# Sheet_1.net
KiCad netlist of a schematic drawn in EasyEDA
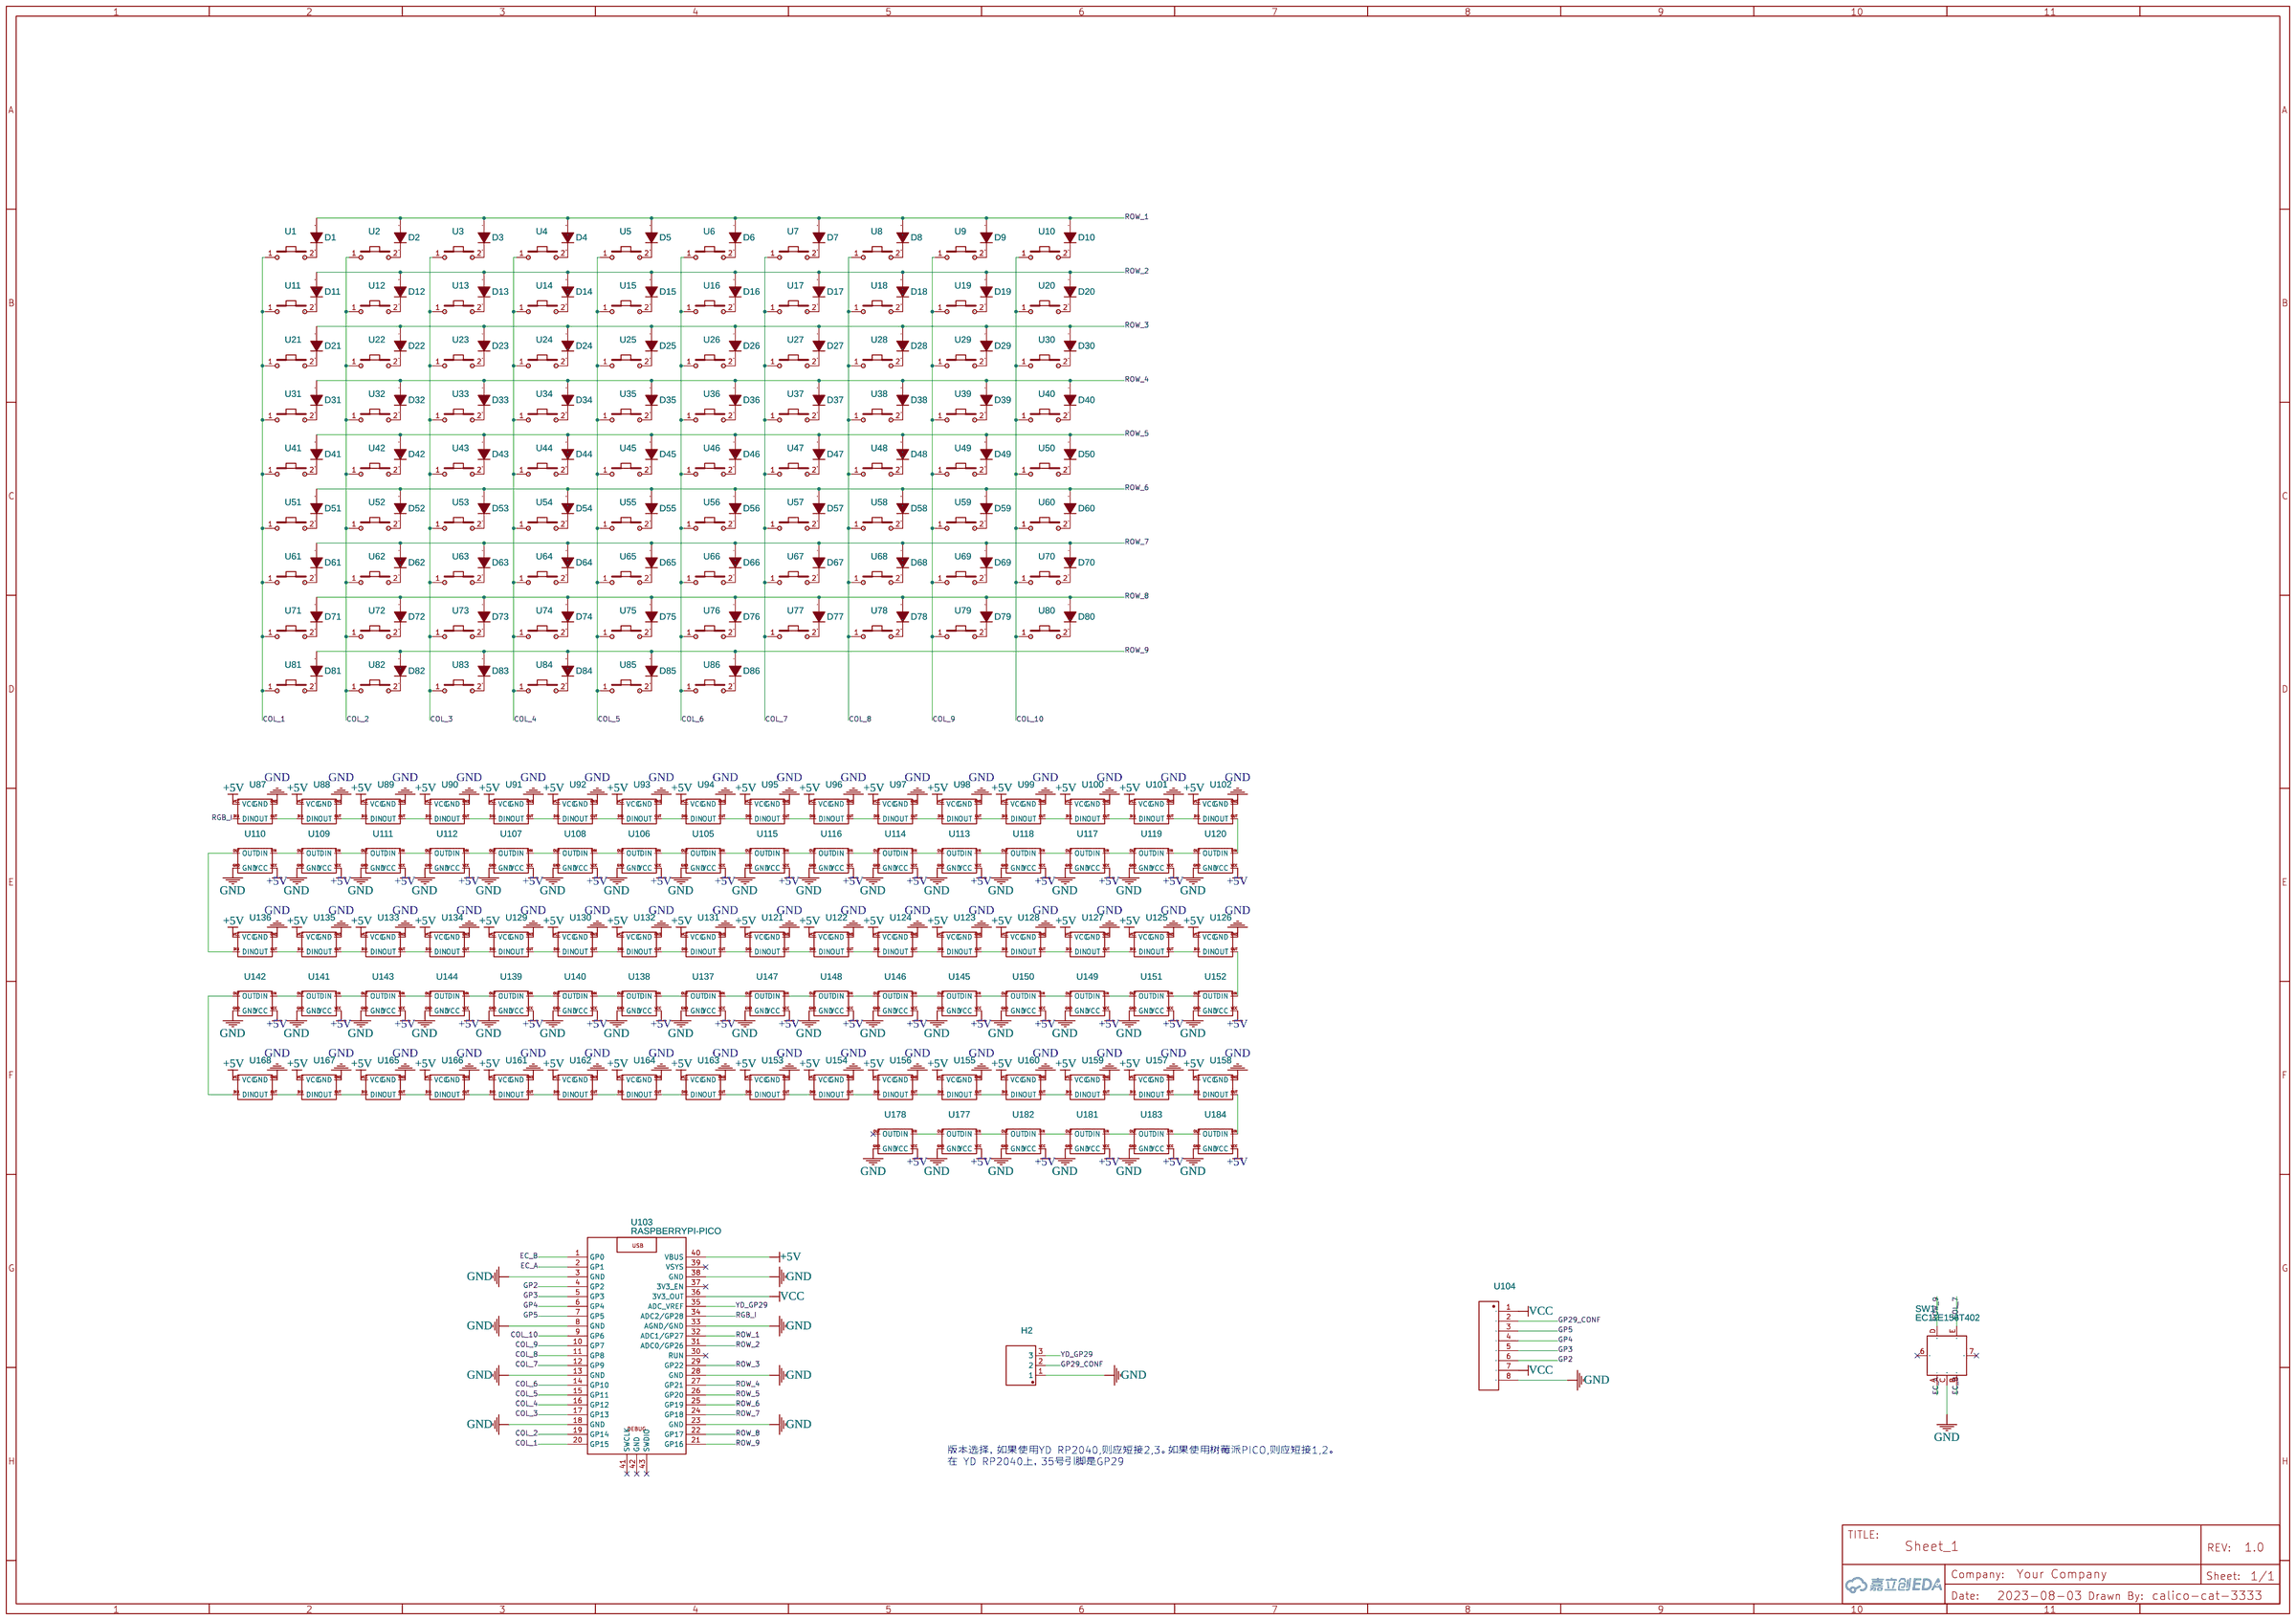
[diagram p0: schematic sheet]

(export (version "E")
  (design (tool "Eeschema 10.0.6"))
  (components
    (comp (ref "D1")
      (value "TC1N4148T26B")
      (fields (field (name "Manufacturer") "TC(德昌)"))
      (libsource (lib "") (part "TC1N4148T26B"))
    )
    (comp (ref "D2")
      (value "TC1N4148T26B")
      (fields (field (name "Manufacturer") "TC(德昌)"))
      (libsource (lib "") (part "TC1N4148T26B"))
    )
    (comp (ref "D3")
      (value "TC1N4148T26B")
      (fields (field (name "Manufacturer") "TC(德昌)"))
      (libsource (lib "") (part "TC1N4148T26B"))
    )
    (comp (ref "D4")
      (value "TC1N4148T26B")
      (fields (field (name "Manufacturer") "TC(德昌)"))
      (libsource (lib "") (part "TC1N4148T26B"))
    )
    (comp (ref "D5")
      (value "TC1N4148T26B")
      (fields (field (name "Manufacturer") "TC(德昌)"))
      (libsource (lib "") (part "TC1N4148T26B"))
    )
    (comp (ref "D6")
      (value "TC1N4148T26B")
      (fields (field (name "Manufacturer") "TC(德昌)"))
      (libsource (lib "") (part "TC1N4148T26B"))
    )
    (comp (ref "D7")
      (value "TC1N4148T26B")
      (fields (field (name "Manufacturer") "TC(德昌)"))
      (libsource (lib "") (part "TC1N4148T26B"))
    )
    (comp (ref "D8")
      (value "TC1N4148T26B")
      (fields (field (name "Manufacturer") "TC(德昌)"))
      (libsource (lib "") (part "TC1N4148T26B"))
    )
    (comp (ref "D9")
      (value "TC1N4148T26B")
      (fields (field (name "Manufacturer") "TC(德昌)"))
      (libsource (lib "") (part "TC1N4148T26B"))
    )
    (comp (ref "D10")
      (value "TC1N4148T26B")
      (fields (field (name "Manufacturer") "TC(德昌)"))
      (libsource (lib "") (part "TC1N4148T26B"))
    )
    (comp (ref "D11")
      (value "TC1N4148T26B")
      (fields (field (name "Manufacturer") "TC(德昌)"))
      (libsource (lib "") (part "TC1N4148T26B"))
    )
    (comp (ref "D12")
      (value "TC1N4148T26B")
      (fields (field (name "Manufacturer") "TC(德昌)"))
      (libsource (lib "") (part "TC1N4148T26B"))
    )
    (comp (ref "D13")
      (value "TC1N4148T26B")
      (fields (field (name "Manufacturer") "TC(德昌)"))
      (libsource (lib "") (part "TC1N4148T26B"))
    )
    (comp (ref "D14")
      (value "TC1N4148T26B")
      (fields (field (name "Manufacturer") "TC(德昌)"))
      (libsource (lib "") (part "TC1N4148T26B"))
    )
    (comp (ref "D15")
      (value "TC1N4148T26B")
      (fields (field (name "Manufacturer") "TC(德昌)"))
      (libsource (lib "") (part "TC1N4148T26B"))
    )
    (comp (ref "D16")
      (value "TC1N4148T26B")
      (fields (field (name "Manufacturer") "TC(德昌)"))
      (libsource (lib "") (part "TC1N4148T26B"))
    )
    (comp (ref "D17")
      (value "TC1N4148T26B")
      (fields (field (name "Manufacturer") "TC(德昌)"))
      (libsource (lib "") (part "TC1N4148T26B"))
    )
    (comp (ref "D18")
      (value "TC1N4148T26B")
      (fields (field (name "Manufacturer") "TC(德昌)"))
      (libsource (lib "") (part "TC1N4148T26B"))
    )
    (comp (ref "D19")
      (value "TC1N4148T26B")
      (fields (field (name "Manufacturer") "TC(德昌)"))
      (libsource (lib "") (part "TC1N4148T26B"))
    )
    (comp (ref "D20")
      (value "TC1N4148T26B")
      (fields (field (name "Manufacturer") "TC(德昌)"))
      (libsource (lib "") (part "TC1N4148T26B"))
    )
    (comp (ref "D21")
      (value "TC1N4148T26B")
      (fields (field (name "Manufacturer") "TC(德昌)"))
      (libsource (lib "") (part "TC1N4148T26B"))
    )
    (comp (ref "D22")
      (value "TC1N4148T26B")
      (fields (field (name "Manufacturer") "TC(德昌)"))
      (libsource (lib "") (part "TC1N4148T26B"))
    )
    (comp (ref "D23")
      (value "TC1N4148T26B")
      (fields (field (name "Manufacturer") "TC(德昌)"))
      (libsource (lib "") (part "TC1N4148T26B"))
    )
    (comp (ref "D24")
      (value "TC1N4148T26B")
      (fields (field (name "Manufacturer") "TC(德昌)"))
      (libsource (lib "") (part "TC1N4148T26B"))
    )
    (comp (ref "D25")
      (value "TC1N4148T26B")
      (fields (field (name "Manufacturer") "TC(德昌)"))
      (libsource (lib "") (part "TC1N4148T26B"))
    )
    (comp (ref "D26")
      (value "TC1N4148T26B")
      (fields (field (name "Manufacturer") "TC(德昌)"))
      (libsource (lib "") (part "TC1N4148T26B"))
    )
    (comp (ref "D27")
      (value "TC1N4148T26B")
      (fields (field (name "Manufacturer") "TC(德昌)"))
      (libsource (lib "") (part "TC1N4148T26B"))
    )
    (comp (ref "D28")
      (value "TC1N4148T26B")
      (fields (field (name "Manufacturer") "TC(德昌)"))
      (libsource (lib "") (part "TC1N4148T26B"))
    )
    (comp (ref "D29")
      (value "TC1N4148T26B")
      (fields (field (name "Manufacturer") "TC(德昌)"))
      (libsource (lib "") (part "TC1N4148T26B"))
    )
    (comp (ref "D30")
      (value "TC1N4148T26B")
      (fields (field (name "Manufacturer") "TC(德昌)"))
      (libsource (lib "") (part "TC1N4148T26B"))
    )
    (comp (ref "D31")
      (value "TC1N4148T26B")
      (fields (field (name "Manufacturer") "TC(德昌)"))
      (libsource (lib "") (part "TC1N4148T26B"))
    )
    (comp (ref "D32")
      (value "TC1N4148T26B")
      (fields (field (name "Manufacturer") "TC(德昌)"))
      (libsource (lib "") (part "TC1N4148T26B"))
    )
    (comp (ref "D33")
      (value "TC1N4148T26B")
      (fields (field (name "Manufacturer") "TC(德昌)"))
      (libsource (lib "") (part "TC1N4148T26B"))
    )
    (comp (ref "D34")
      (value "TC1N4148T26B")
      (fields (field (name "Manufacturer") "TC(德昌)"))
      (libsource (lib "") (part "TC1N4148T26B"))
    )
    (comp (ref "D35")
      (value "TC1N4148T26B")
      (fields (field (name "Manufacturer") "TC(德昌)"))
      (libsource (lib "") (part "TC1N4148T26B"))
    )
    (comp (ref "D36")
      (value "TC1N4148T26B")
      (fields (field (name "Manufacturer") "TC(德昌)"))
      (libsource (lib "") (part "TC1N4148T26B"))
    )
    (comp (ref "D37")
      (value "TC1N4148T26B")
      (fields (field (name "Manufacturer") "TC(德昌)"))
      (libsource (lib "") (part "TC1N4148T26B"))
    )
    (comp (ref "D38")
      (value "TC1N4148T26B")
      (fields (field (name "Manufacturer") "TC(德昌)"))
      (libsource (lib "") (part "TC1N4148T26B"))
    )
    (comp (ref "D39")
      (value "TC1N4148T26B")
      (fields (field (name "Manufacturer") "TC(德昌)"))
      (libsource (lib "") (part "TC1N4148T26B"))
    )
    (comp (ref "D40")
      (value "TC1N4148T26B")
      (fields (field (name "Manufacturer") "TC(德昌)"))
      (libsource (lib "") (part "TC1N4148T26B"))
    )
    (comp (ref "D41")
      (value "TC1N4148T26B")
      (fields (field (name "Manufacturer") "TC(德昌)"))
      (libsource (lib "") (part "TC1N4148T26B"))
    )
    (comp (ref "D42")
      (value "TC1N4148T26B")
      (fields (field (name "Manufacturer") "TC(德昌)"))
      (libsource (lib "") (part "TC1N4148T26B"))
    )
    (comp (ref "D43")
      (value "TC1N4148T26B")
      (fields (field (name "Manufacturer") "TC(德昌)"))
      (libsource (lib "") (part "TC1N4148T26B"))
    )
    (comp (ref "D44")
      (value "TC1N4148T26B")
      (fields (field (name "Manufacturer") "TC(德昌)"))
      (libsource (lib "") (part "TC1N4148T26B"))
    )
    (comp (ref "D45")
      (value "TC1N4148T26B")
      (fields (field (name "Manufacturer") "TC(德昌)"))
      (libsource (lib "") (part "TC1N4148T26B"))
    )
    (comp (ref "D46")
      (value "TC1N4148T26B")
      (fields (field (name "Manufacturer") "TC(德昌)"))
      (libsource (lib "") (part "TC1N4148T26B"))
    )
    (comp (ref "D47")
      (value "TC1N4148T26B")
      (fields (field (name "Manufacturer") "TC(德昌)"))
      (libsource (lib "") (part "TC1N4148T26B"))
    )
    (comp (ref "D48")
      (value "TC1N4148T26B")
      (fields (field (name "Manufacturer") "TC(德昌)"))
      (libsource (lib "") (part "TC1N4148T26B"))
    )
    (comp (ref "D49")
      (value "TC1N4148T26B")
      (fields (field (name "Manufacturer") "TC(德昌)"))
      (libsource (lib "") (part "TC1N4148T26B"))
    )
    (comp (ref "D50")
      (value "TC1N4148T26B")
      (fields (field (name "Manufacturer") "TC(德昌)"))
      (libsource (lib "") (part "TC1N4148T26B"))
    )
    (comp (ref "D51")
      (value "TC1N4148T26B")
      (fields (field (name "Manufacturer") "TC(德昌)"))
      (libsource (lib "") (part "TC1N4148T26B"))
    )
    (comp (ref "D52")
      (value "TC1N4148T26B")
      (fields (field (name "Manufacturer") "TC(德昌)"))
      (libsource (lib "") (part "TC1N4148T26B"))
    )
    (comp (ref "D53")
      (value "TC1N4148T26B")
      (fields (field (name "Manufacturer") "TC(德昌)"))
      (libsource (lib "") (part "TC1N4148T26B"))
    )
    (comp (ref "D54")
      (value "TC1N4148T26B")
      (fields (field (name "Manufacturer") "TC(德昌)"))
      (libsource (lib "") (part "TC1N4148T26B"))
    )
    (comp (ref "D55")
      (value "TC1N4148T26B")
      (fields (field (name "Manufacturer") "TC(德昌)"))
      (libsource (lib "") (part "TC1N4148T26B"))
    )
    (comp (ref "D56")
      (value "TC1N4148T26B")
      (fields (field (name "Manufacturer") "TC(德昌)"))
      (libsource (lib "") (part "TC1N4148T26B"))
    )
    (comp (ref "D57")
      (value "TC1N4148T26B")
      (fields (field (name "Manufacturer") "TC(德昌)"))
      (libsource (lib "") (part "TC1N4148T26B"))
    )
    (comp (ref "D58")
      (value "TC1N4148T26B")
      (fields (field (name "Manufacturer") "TC(德昌)"))
      (libsource (lib "") (part "TC1N4148T26B"))
    )
    (comp (ref "D59")
      (value "TC1N4148T26B")
      (fields (field (name "Manufacturer") "TC(德昌)"))
      (libsource (lib "") (part "TC1N4148T26B"))
    )
    (comp (ref "D60")
      (value "TC1N4148T26B")
      (fields (field (name "Manufacturer") "TC(德昌)"))
      (libsource (lib "") (part "TC1N4148T26B"))
    )
    (comp (ref "D61")
      (value "TC1N4148T26B")
      (fields (field (name "Manufacturer") "TC(德昌)"))
      (libsource (lib "") (part "TC1N4148T26B"))
    )
    (comp (ref "D62")
      (value "TC1N4148T26B")
      (fields (field (name "Manufacturer") "TC(德昌)"))
      (libsource (lib "") (part "TC1N4148T26B"))
    )
    (comp (ref "D63")
      (value "TC1N4148T26B")
      (fields (field (name "Manufacturer") "TC(德昌)"))
      (libsource (lib "") (part "TC1N4148T26B"))
    )
    (comp (ref "D64")
      (value "TC1N4148T26B")
      (fields (field (name "Manufacturer") "TC(德昌)"))
      (libsource (lib "") (part "TC1N4148T26B"))
    )
    (comp (ref "D65")
      (value "TC1N4148T26B")
      (fields (field (name "Manufacturer") "TC(德昌)"))
      (libsource (lib "") (part "TC1N4148T26B"))
    )
    (comp (ref "D66")
      (value "TC1N4148T26B")
      (fields (field (name "Manufacturer") "TC(德昌)"))
      (libsource (lib "") (part "TC1N4148T26B"))
    )
    (comp (ref "D67")
      (value "TC1N4148T26B")
      (fields (field (name "Manufacturer") "TC(德昌)"))
      (libsource (lib "") (part "TC1N4148T26B"))
    )
    (comp (ref "D68")
      (value "TC1N4148T26B")
      (fields (field (name "Manufacturer") "TC(德昌)"))
      (libsource (lib "") (part "TC1N4148T26B"))
    )
    (comp (ref "D69")
      (value "TC1N4148T26B")
      (fields (field (name "Manufacturer") "TC(德昌)"))
      (libsource (lib "") (part "TC1N4148T26B"))
    )
    (comp (ref "D70")
      (value "TC1N4148T26B")
      (fields (field (name "Manufacturer") "TC(德昌)"))
      (libsource (lib "") (part "TC1N4148T26B"))
    )
    (comp (ref "D71")
      (value "TC1N4148T26B")
      (fields (field (name "Manufacturer") "TC(德昌)"))
      (libsource (lib "") (part "TC1N4148T26B"))
    )
    (comp (ref "D72")
      (value "TC1N4148T26B")
      (fields (field (name "Manufacturer") "TC(德昌)"))
      (libsource (lib "") (part "TC1N4148T26B"))
    )
    (comp (ref "D73")
      (value "TC1N4148T26B")
      (fields (field (name "Manufacturer") "TC(德昌)"))
      (libsource (lib "") (part "TC1N4148T26B"))
    )
    (comp (ref "D74")
      (value "TC1N4148T26B")
      (fields (field (name "Manufacturer") "TC(德昌)"))
      (libsource (lib "") (part "TC1N4148T26B"))
    )
    (comp (ref "D75")
      (value "TC1N4148T26B")
      (fields (field (name "Manufacturer") "TC(德昌)"))
      (libsource (lib "") (part "TC1N4148T26B"))
    )
    (comp (ref "D76")
      (value "TC1N4148T26B")
      (fields (field (name "Manufacturer") "TC(德昌)"))
      (libsource (lib "") (part "TC1N4148T26B"))
    )
    (comp (ref "D77")
      (value "TC1N4148T26B")
      (fields (field (name "Manufacturer") "TC(德昌)"))
      (libsource (lib "") (part "TC1N4148T26B"))
    )
    (comp (ref "D78")
      (value "TC1N4148T26B")
      (fields (field (name "Manufacturer") "TC(德昌)"))
      (libsource (lib "") (part "TC1N4148T26B"))
    )
    (comp (ref "D79")
      (value "TC1N4148T26B")
      (fields (field (name "Manufacturer") "TC(德昌)"))
      (libsource (lib "") (part "TC1N4148T26B"))
    )
    (comp (ref "D80")
      (value "TC1N4148T26B")
      (fields (field (name "Manufacturer") "TC(德昌)"))
      (libsource (lib "") (part "TC1N4148T26B"))
    )
    (comp (ref "D81")
      (value "TC1N4148T26B")
      (fields (field (name "Manufacturer") "TC(德昌)"))
      (libsource (lib "") (part "TC1N4148T26B"))
    )
    (comp (ref "D82")
      (value "TC1N4148T26B")
      (fields (field (name "Manufacturer") "TC(德昌)"))
      (libsource (lib "") (part "TC1N4148T26B"))
    )
    (comp (ref "D83")
      (value "TC1N4148T26B")
      (fields (field (name "Manufacturer") "TC(德昌)"))
      (libsource (lib "") (part "TC1N4148T26B"))
    )
    (comp (ref "D84")
      (value "TC1N4148T26B")
      (fields (field (name "Manufacturer") "TC(德昌)"))
      (libsource (lib "") (part "TC1N4148T26B"))
    )
    (comp (ref "D85")
      (value "TC1N4148T26B")
      (fields (field (name "Manufacturer") "TC(德昌)"))
      (libsource (lib "") (part "TC1N4148T26B"))
    )
    (comp (ref "D86")
      (value "TC1N4148T26B")
      (fields (field (name "Manufacturer") "TC(德昌)"))
      (libsource (lib "") (part "TC1N4148T26B"))
    )
    (comp (ref "H2")
      (value "210S-1*3P L=11.6MMGold-plated black")
      (fields (field (name "Manufacturer Part") "B-2100S03P-A110") (field (name "Manufacturer") "Ckmtw(灿科盟)"))
      (libsource (lib "") (part "210S-1*3P L=11.6MMGold-plated black"))
    )
    (comp (ref "SW1")
      (value "EC11E156T402")
      (fields (field (name "Manufacturer") "ALPSALPINE(阿尔卑斯阿尔派)"))
      (libsource (lib "") (part "EC11E156T402"))
    )
    (comp (ref "U1") (value "U90") (libsource (lib "") (part "轴座")))
    (comp (ref "U2") (value "U90") (libsource (lib "") (part "轴座")))
    (comp (ref "U3") (value "U90") (libsource (lib "") (part "轴座")))
    (comp (ref "U4") (value "U90") (libsource (lib "") (part "轴座")))
    (comp (ref "U5") (value "U90") (libsource (lib "") (part "轴座")))
    (comp (ref "U6") (value "U90") (libsource (lib "") (part "轴座")))
    (comp (ref "U7") (value "U90") (libsource (lib "") (part "轴座")))
    (comp (ref "U8") (value "U90") (libsource (lib "") (part "轴座")))
    (comp (ref "U9") (value "U90") (libsource (lib "") (part "轴座")))
    (comp (ref "U10") (value "U90") (libsource (lib "") (part "轴座")))
    (comp (ref "U11") (value "U90") (libsource (lib "") (part "轴座")))
    (comp (ref "U12") (value "U90") (libsource (lib "") (part "轴座")))
    (comp (ref "U13") (value "U90") (libsource (lib "") (part "轴座")))
    (comp (ref "U14") (value "U90") (libsource (lib "") (part "轴座")))
    (comp (ref "U15") (value "U90") (libsource (lib "") (part "轴座")))
    (comp (ref "U16") (value "U90") (libsource (lib "") (part "轴座")))
    (comp (ref "U17") (value "U90") (libsource (lib "") (part "轴座")))
    (comp (ref "U18") (value "U90") (libsource (lib "") (part "轴座")))
    (comp (ref "U19") (value "U90") (libsource (lib "") (part "轴座")))
    (comp (ref "U20") (value "U90") (libsource (lib "") (part "轴座")))
    (comp (ref "U21") (value "U90") (libsource (lib "") (part "轴座")))
    (comp (ref "U22") (value "U90") (libsource (lib "") (part "轴座")))
    (comp (ref "U23") (value "U90") (libsource (lib "") (part "轴座")))
    (comp (ref "U24") (value "U90") (libsource (lib "") (part "轴座")))
    (comp (ref "U25") (value "U90") (libsource (lib "") (part "轴座")))
    (comp (ref "U26") (value "U90") (libsource (lib "") (part "轴座")))
    (comp (ref "U27") (value "U90") (libsource (lib "") (part "轴座")))
    (comp (ref "U28") (value "U90") (libsource (lib "") (part "轴座")))
    (comp (ref "U29") (value "U90") (libsource (lib "") (part "轴座")))
    (comp (ref "U30") (value "U90") (libsource (lib "") (part "轴座")))
    (comp (ref "U31") (value "U90") (libsource (lib "") (part "轴座")))
    (comp (ref "U32") (value "U90") (libsource (lib "") (part "轴座")))
    (comp (ref "U33") (value "U90") (libsource (lib "") (part "轴座")))
    (comp (ref "U34") (value "U90") (libsource (lib "") (part "轴座")))
    (comp (ref "U35") (value "U90") (libsource (lib "") (part "轴座")))
    (comp (ref "U36") (value "U90") (libsource (lib "") (part "轴座")))
    (comp (ref "U37") (value "U90") (libsource (lib "") (part "轴座")))
    (comp (ref "U38") (value "U90") (libsource (lib "") (part "轴座")))
    (comp (ref "U39") (value "U90") (libsource (lib "") (part "轴座")))
    (comp (ref "U40") (value "U90") (libsource (lib "") (part "轴座")))
    (comp (ref "U41") (value "U90") (libsource (lib "") (part "轴座")))
    (comp (ref "U42") (value "U90") (libsource (lib "") (part "轴座")))
    (comp (ref "U43") (value "U90") (libsource (lib "") (part "轴座")))
    (comp (ref "U44") (value "U90") (libsource (lib "") (part "轴座")))
    (comp (ref "U45") (value "U90") (libsource (lib "") (part "轴座")))
    (comp (ref "U46") (value "U90") (libsource (lib "") (part "轴座")))
    (comp (ref "U47") (value "U90") (libsource (lib "") (part "轴座")))
    (comp (ref "U48") (value "U90") (libsource (lib "") (part "轴座")))
    (comp (ref "U49") (value "U90") (libsource (lib "") (part "轴座")))
    (comp (ref "U50") (value "U90") (libsource (lib "") (part "轴座")))
    (comp (ref "U51") (value "U90") (libsource (lib "") (part "轴座")))
    (comp (ref "U52") (value "U90") (libsource (lib "") (part "轴座")))
    (comp (ref "U53") (value "U90") (libsource (lib "") (part "轴座")))
    (comp (ref "U54") (value "U90") (libsource (lib "") (part "轴座")))
    (comp (ref "U55") (value "U90") (libsource (lib "") (part "轴座")))
    (comp (ref "U56") (value "U90") (libsource (lib "") (part "轴座")))
    (comp (ref "U57") (value "U90") (libsource (lib "") (part "轴座")))
    (comp (ref "U58") (value "U90") (libsource (lib "") (part "轴座")))
    (comp (ref "U59") (value "U90") (libsource (lib "") (part "轴座")))
    (comp (ref "U60") (value "U90") (libsource (lib "") (part "轴座")))
    (comp (ref "U61") (value "U90") (libsource (lib "") (part "轴座")))
    (comp (ref "U62") (value "U90") (libsource (lib "") (part "轴座")))
    (comp (ref "U63") (value "U90") (libsource (lib "") (part "轴座")))
    (comp (ref "U64") (value "U90") (libsource (lib "") (part "轴座")))
    (comp (ref "U65") (value "U90") (libsource (lib "") (part "轴座")))
    (comp (ref "U66") (value "U90") (libsource (lib "") (part "轴座")))
    (comp (ref "U67") (value "U90") (libsource (lib "") (part "轴座")))
    (comp (ref "U68") (value "U90") (libsource (lib "") (part "轴座")))
    (comp (ref "U69") (value "U90") (libsource (lib "") (part "轴座")))
    (comp (ref "U70") (value "U90") (libsource (lib "") (part "轴座")))
    (comp (ref "U71") (value "U90") (libsource (lib "") (part "轴座")))
    (comp (ref "U72") (value "U90") (libsource (lib "") (part "轴座")))
    (comp (ref "U73") (value "U90") (libsource (lib "") (part "轴座")))
    (comp (ref "U74") (value "U90") (libsource (lib "") (part "轴座")))
    (comp (ref "U75") (value "U90") (libsource (lib "") (part "轴座")))
    (comp (ref "U76") (value "U90") (libsource (lib "") (part "轴座")))
    (comp (ref "U77") (value "U90") (libsource (lib "") (part "轴座")))
    (comp (ref "U78") (value "U90") (libsource (lib "") (part "轴座")))
    (comp (ref "U79") (value "U90") (libsource (lib "") (part "轴座")))
    (comp (ref "U80") (value "U90") (libsource (lib "") (part "轴座")))
    (comp (ref "U81") (value "U90") (libsource (lib "") (part "轴座")))
    (comp (ref "U82") (value "U90") (libsource (lib "") (part "轴座")))
    (comp (ref "U83") (value "U90") (libsource (lib "") (part "轴座")))
    (comp (ref "U84") (value "U90") (libsource (lib "") (part "轴座")))
    (comp (ref "U85") (value "U90") (libsource (lib "") (part "轴座")))
    (comp (ref "U86") (value "U90") (libsource (lib "") (part "轴座")))
    (comp (ref "U87") (value "NO") (libsource (lib "") (part "WS2812-3528")))
    (comp (ref "U88") (value "NO") (libsource (lib "") (part "WS2812-3528")))
    (comp (ref "U89") (value "NO") (libsource (lib "") (part "WS2812-3528")))
    (comp (ref "U90") (value "NO") (libsource (lib "") (part "WS2812-3528")))
    (comp (ref "U91") (value "NO") (libsource (lib "") (part "WS2812-3528")))
    (comp (ref "U92") (value "NO") (libsource (lib "") (part "WS2812-3528")))
    (comp (ref "U93") (value "NO") (libsource (lib "") (part "WS2812-3528")))
    (comp (ref "U94") (value "NO") (libsource (lib "") (part "WS2812-3528")))
    (comp (ref "U95") (value "NO") (libsource (lib "") (part "WS2812-3528")))
    (comp (ref "U96") (value "NO") (libsource (lib "") (part "WS2812-3528")))
    (comp (ref "U97") (value "NO") (libsource (lib "") (part "WS2812-3528")))
    (comp (ref "U98") (value "NO") (libsource (lib "") (part "WS2812-3528")))
    (comp (ref "U99") (value "NO") (libsource (lib "") (part "WS2812-3528")))
    (comp (ref "U100") (value "NO") (libsource (lib "") (part "WS2812-3528")))
    (comp (ref "U101") (value "NO") (libsource (lib "") (part "WS2812-3528")))
    (comp (ref "U102") (value "NO") (libsource (lib "") (part "WS2812-3528")))
    (comp (ref "U103") (value "RASPBERRYPI-PICO") (libsource (lib "") (part "RASPBERRYPI-PICO")))
    (comp (ref "U104") (value "U82") (libsource (lib "") (part "排针 8P")))
    (comp (ref "U105") (value "NO") (libsource (lib "") (part "WS2812-3528_1")))
    (comp (ref "U106") (value "NO") (libsource (lib "") (part "WS2812-3528_1")))
    (comp (ref "U107") (value "NO") (libsource (lib "") (part "WS2812-3528_1")))
    (comp (ref "U108") (value "NO") (libsource (lib "") (part "WS2812-3528_1")))
    (comp (ref "U109") (value "NO") (libsource (lib "") (part "WS2812-3528_1")))
    (comp (ref "U110") (value "NO") (libsource (lib "") (part "WS2812-3528_1")))
    (comp (ref "U111") (value "NO") (libsource (lib "") (part "WS2812-3528_1")))
    (comp (ref "U112") (value "NO") (libsource (lib "") (part "WS2812-3528_1")))
    (comp (ref "U113") (value "NO") (libsource (lib "") (part "WS2812-3528_1")))
    (comp (ref "U114") (value "NO") (libsource (lib "") (part "WS2812-3528_1")))
    (comp (ref "U115") (value "NO") (libsource (lib "") (part "WS2812-3528_1")))
    (comp (ref "U116") (value "NO") (libsource (lib "") (part "WS2812-3528_1")))
    (comp (ref "U117") (value "NO") (libsource (lib "") (part "WS2812-3528_1")))
    (comp (ref "U118") (value "NO") (libsource (lib "") (part "WS2812-3528_1")))
    (comp (ref "U119") (value "NO") (libsource (lib "") (part "WS2812-3528_1")))
    (comp (ref "U120") (value "NO") (libsource (lib "") (part "WS2812-3528_1")))
    (comp (ref "U121") (value "NO") (libsource (lib "") (part "WS2812-3528")))
    (comp (ref "U122") (value "NO") (libsource (lib "") (part "WS2812-3528")))
    (comp (ref "U123") (value "NO") (libsource (lib "") (part "WS2812-3528")))
    (comp (ref "U124") (value "NO") (libsource (lib "") (part "WS2812-3528")))
    (comp (ref "U125") (value "NO") (libsource (lib "") (part "WS2812-3528")))
    (comp (ref "U126") (value "NO") (libsource (lib "") (part "WS2812-3528")))
    (comp (ref "U127") (value "NO") (libsource (lib "") (part "WS2812-3528")))
    (comp (ref "U128") (value "NO") (libsource (lib "") (part "WS2812-3528")))
    (comp (ref "U129") (value "NO") (libsource (lib "") (part "WS2812-3528")))
    (comp (ref "U130") (value "NO") (libsource (lib "") (part "WS2812-3528")))
    (comp (ref "U131") (value "NO") (libsource (lib "") (part "WS2812-3528")))
    (comp (ref "U132") (value "NO") (libsource (lib "") (part "WS2812-3528")))
    (comp (ref "U133") (value "NO") (libsource (lib "") (part "WS2812-3528")))
    (comp (ref "U134") (value "NO") (libsource (lib "") (part "WS2812-3528")))
    (comp (ref "U135") (value "NO") (libsource (lib "") (part "WS2812-3528")))
    (comp (ref "U136") (value "NO") (libsource (lib "") (part "WS2812-3528")))
    (comp (ref "U137") (value "NO") (libsource (lib "") (part "WS2812-3528_1")))
    (comp (ref "U138") (value "NO") (libsource (lib "") (part "WS2812-3528_1")))
    (comp (ref "U139") (value "NO") (libsource (lib "") (part "WS2812-3528_1")))
    (comp (ref "U140") (value "NO") (libsource (lib "") (part "WS2812-3528_1")))
    (comp (ref "U141") (value "NO") (libsource (lib "") (part "WS2812-3528_1")))
    (comp (ref "U142") (value "NO") (libsource (lib "") (part "WS2812-3528_1")))
    (comp (ref "U143") (value "NO") (libsource (lib "") (part "WS2812-3528_1")))
    (comp (ref "U144") (value "NO") (libsource (lib "") (part "WS2812-3528_1")))
    (comp (ref "U145") (value "NO") (libsource (lib "") (part "WS2812-3528_1")))
    (comp (ref "U146") (value "NO") (libsource (lib "") (part "WS2812-3528_1")))
    (comp (ref "U147") (value "NO") (libsource (lib "") (part "WS2812-3528_1")))
    (comp (ref "U148") (value "NO") (libsource (lib "") (part "WS2812-3528_1")))
    (comp (ref "U149") (value "NO") (libsource (lib "") (part "WS2812-3528_1")))
    (comp (ref "U150") (value "NO") (libsource (lib "") (part "WS2812-3528_1")))
    (comp (ref "U151") (value "NO") (libsource (lib "") (part "WS2812-3528_1")))
    (comp (ref "U152") (value "NO") (libsource (lib "") (part "WS2812-3528_1")))
    (comp (ref "U153") (value "NO") (libsource (lib "") (part "WS2812-3528")))
    (comp (ref "U154") (value "NO") (libsource (lib "") (part "WS2812-3528")))
    (comp (ref "U155") (value "NO") (libsource (lib "") (part "WS2812-3528")))
    (comp (ref "U156") (value "NO") (libsource (lib "") (part "WS2812-3528")))
    (comp (ref "U157") (value "NO") (libsource (lib "") (part "WS2812-3528")))
    (comp (ref "U158") (value "NO") (libsource (lib "") (part "WS2812-3528")))
    (comp (ref "U159") (value "NO") (libsource (lib "") (part "WS2812-3528")))
    (comp (ref "U160") (value "NO") (libsource (lib "") (part "WS2812-3528")))
    (comp (ref "U161") (value "NO") (libsource (lib "") (part "WS2812-3528")))
    (comp (ref "U162") (value "NO") (libsource (lib "") (part "WS2812-3528")))
    (comp (ref "U163") (value "NO") (libsource (lib "") (part "WS2812-3528")))
    (comp (ref "U164") (value "NO") (libsource (lib "") (part "WS2812-3528")))
    (comp (ref "U165") (value "NO") (libsource (lib "") (part "WS2812-3528")))
    (comp (ref "U166") (value "NO") (libsource (lib "") (part "WS2812-3528")))
    (comp (ref "U167") (value "NO") (libsource (lib "") (part "WS2812-3528")))
    (comp (ref "U168") (value "NO") (libsource (lib "") (part "WS2812-3528")))
    (comp (ref "U177") (value "NO") (libsource (lib "") (part "WS2812-3528_1")))
    (comp (ref "U178") (value "NO") (libsource (lib "") (part "WS2812-3528_1")))
    (comp (ref "U181") (value "NO") (libsource (lib "") (part "WS2812-3528_1")))
    (comp (ref "U182") (value "NO") (libsource (lib "") (part "WS2812-3528_1")))
    (comp (ref "U183") (value "NO") (libsource (lib "") (part "WS2812-3528_1")))
    (comp (ref "U184") (value "NO") (libsource (lib "") (part "WS2812-3528_1")))
  )
  (nets
    (net (code "1") (name "+5V") (class "Default")
      (node (ref "U100") (pin "VCC") (pinfunction "VCC_VCC") (pintype "unspecified"))
      (node (ref "U101") (pin "VCC") (pinfunction "VCC_VCC") (pintype "unspecified"))
      (node (ref "U102") (pin "VCC") (pinfunction "VCC_VCC") (pintype "unspecified"))
      (node (ref "U103") (pin "40") (pinfunction "VBUS_40") (pintype "passive"))
      (node (ref "U105") (pin "VCC") (pinfunction "VCC_VCC") (pintype "unspecified"))
      (node (ref "U106") (pin "VCC") (pinfunction "VCC_VCC") (pintype "unspecified"))
      (node (ref "U107") (pin "VCC") (pinfunction "VCC_VCC") (pintype "unspecified"))
      (node (ref "U108") (pin "VCC") (pinfunction "VCC_VCC") (pintype "unspecified"))
      (node (ref "U109") (pin "VCC") (pinfunction "VCC_VCC") (pintype "unspecified"))
      (node (ref "U110") (pin "VCC") (pinfunction "VCC_VCC") (pintype "unspecified"))
      (node (ref "U111") (pin "VCC") (pinfunction "VCC_VCC") (pintype "unspecified"))
      (node (ref "U112") (pin "VCC") (pinfunction "VCC_VCC") (pintype "unspecified"))
      (node (ref "U113") (pin "VCC") (pinfunction "VCC_VCC") (pintype "unspecified"))
      (node (ref "U114") (pin "VCC") (pinfunction "VCC_VCC") (pintype "unspecified"))
      (node (ref "U115") (pin "VCC") (pinfunction "VCC_VCC") (pintype "unspecified"))
      (node (ref "U116") (pin "VCC") (pinfunction "VCC_VCC") (pintype "unspecified"))
      (node (ref "U117") (pin "VCC") (pinfunction "VCC_VCC") (pintype "unspecified"))
      (node (ref "U118") (pin "VCC") (pinfunction "VCC_VCC") (pintype "unspecified"))
      (node (ref "U119") (pin "VCC") (pinfunction "VCC_VCC") (pintype "unspecified"))
      (node (ref "U120") (pin "VCC") (pinfunction "VCC_VCC") (pintype "unspecified"))
      (node (ref "U121") (pin "VCC") (pinfunction "VCC_VCC") (pintype "unspecified"))
      (node (ref "U122") (pin "VCC") (pinfunction "VCC_VCC") (pintype "unspecified"))
      (node (ref "U123") (pin "VCC") (pinfunction "VCC_VCC") (pintype "unspecified"))
      (node (ref "U124") (pin "VCC") (pinfunction "VCC_VCC") (pintype "unspecified"))
      (node (ref "U125") (pin "VCC") (pinfunction "VCC_VCC") (pintype "unspecified"))
      (node (ref "U126") (pin "VCC") (pinfunction "VCC_VCC") (pintype "unspecified"))
      (node (ref "U127") (pin "VCC") (pinfunction "VCC_VCC") (pintype "unspecified"))
      (node (ref "U128") (pin "VCC") (pinfunction "VCC_VCC") (pintype "unspecified"))
      (node (ref "U129") (pin "VCC") (pinfunction "VCC_VCC") (pintype "unspecified"))
      (node (ref "U130") (pin "VCC") (pinfunction "VCC_VCC") (pintype "unspecified"))
      (node (ref "U131") (pin "VCC") (pinfunction "VCC_VCC") (pintype "unspecified"))
      (node (ref "U132") (pin "VCC") (pinfunction "VCC_VCC") (pintype "unspecified"))
      (node (ref "U133") (pin "VCC") (pinfunction "VCC_VCC") (pintype "unspecified"))
      (node (ref "U134") (pin "VCC") (pinfunction "VCC_VCC") (pintype "unspecified"))
      (node (ref "U135") (pin "VCC") (pinfunction "VCC_VCC") (pintype "unspecified"))
      (node (ref "U136") (pin "VCC") (pinfunction "VCC_VCC") (pintype "unspecified"))
      (node (ref "U137") (pin "VCC") (pinfunction "VCC_VCC") (pintype "unspecified"))
      (node (ref "U138") (pin "VCC") (pinfunction "VCC_VCC") (pintype "unspecified"))
      (node (ref "U139") (pin "VCC") (pinfunction "VCC_VCC") (pintype "unspecified"))
      (node (ref "U140") (pin "VCC") (pinfunction "VCC_VCC") (pintype "unspecified"))
      (node (ref "U141") (pin "VCC") (pinfunction "VCC_VCC") (pintype "unspecified"))
      (node (ref "U142") (pin "VCC") (pinfunction "VCC_VCC") (pintype "unspecified"))
      (node (ref "U143") (pin "VCC") (pinfunction "VCC_VCC") (pintype "unspecified"))
      (node (ref "U144") (pin "VCC") (pinfunction "VCC_VCC") (pintype "unspecified"))
      (node (ref "U145") (pin "VCC") (pinfunction "VCC_VCC") (pintype "unspecified"))
      (node (ref "U146") (pin "VCC") (pinfunction "VCC_VCC") (pintype "unspecified"))
      (node (ref "U147") (pin "VCC") (pinfunction "VCC_VCC") (pintype "unspecified"))
      (node (ref "U148") (pin "VCC") (pinfunction "VCC_VCC") (pintype "unspecified"))
      (node (ref "U149") (pin "VCC") (pinfunction "VCC_VCC") (pintype "unspecified"))
      (node (ref "U150") (pin "VCC") (pinfunction "VCC_VCC") (pintype "unspecified"))
      (node (ref "U151") (pin "VCC") (pinfunction "VCC_VCC") (pintype "unspecified"))
      (node (ref "U152") (pin "VCC") (pinfunction "VCC_VCC") (pintype "unspecified"))
      (node (ref "U153") (pin "VCC") (pinfunction "VCC_VCC") (pintype "unspecified"))
      (node (ref "U154") (pin "VCC") (pinfunction "VCC_VCC") (pintype "unspecified"))
      (node (ref "U155") (pin "VCC") (pinfunction "VCC_VCC") (pintype "unspecified"))
      (node (ref "U156") (pin "VCC") (pinfunction "VCC_VCC") (pintype "unspecified"))
      (node (ref "U157") (pin "VCC") (pinfunction "VCC_VCC") (pintype "unspecified"))
      (node (ref "U158") (pin "VCC") (pinfunction "VCC_VCC") (pintype "unspecified"))
      (node (ref "U159") (pin "VCC") (pinfunction "VCC_VCC") (pintype "unspecified"))
      (node (ref "U160") (pin "VCC") (pinfunction "VCC_VCC") (pintype "unspecified"))
      (node (ref "U161") (pin "VCC") (pinfunction "VCC_VCC") (pintype "unspecified"))
      (node (ref "U162") (pin "VCC") (pinfunction "VCC_VCC") (pintype "unspecified"))
      (node (ref "U163") (pin "VCC") (pinfunction "VCC_VCC") (pintype "unspecified"))
      (node (ref "U164") (pin "VCC") (pinfunction "VCC_VCC") (pintype "unspecified"))
      (node (ref "U165") (pin "VCC") (pinfunction "VCC_VCC") (pintype "unspecified"))
      (node (ref "U166") (pin "VCC") (pinfunction "VCC_VCC") (pintype "unspecified"))
      (node (ref "U167") (pin "VCC") (pinfunction "VCC_VCC") (pintype "unspecified"))
      (node (ref "U168") (pin "VCC") (pinfunction "VCC_VCC") (pintype "unspecified"))
      (node (ref "U177") (pin "VCC") (pinfunction "VCC_VCC") (pintype "unspecified"))
      (node (ref "U178") (pin "VCC") (pinfunction "VCC_VCC") (pintype "unspecified"))
      (node (ref "U181") (pin "VCC") (pinfunction "VCC_VCC") (pintype "unspecified"))
      (node (ref "U182") (pin "VCC") (pinfunction "VCC_VCC") (pintype "unspecified"))
      (node (ref "U183") (pin "VCC") (pinfunction "VCC_VCC") (pintype "unspecified"))
      (node (ref "U184") (pin "VCC") (pinfunction "VCC_VCC") (pintype "unspecified"))
      (node (ref "U87") (pin "VCC") (pinfunction "VCC_VCC") (pintype "unspecified"))
      (node (ref "U88") (pin "VCC") (pinfunction "VCC_VCC") (pintype "unspecified"))
      (node (ref "U89") (pin "VCC") (pinfunction "VCC_VCC") (pintype "unspecified"))
      (node (ref "U90") (pin "VCC") (pinfunction "VCC_VCC") (pintype "unspecified"))
      (node (ref "U91") (pin "VCC") (pinfunction "VCC_VCC") (pintype "unspecified"))
      (node (ref "U92") (pin "VCC") (pinfunction "VCC_VCC") (pintype "unspecified"))
      (node (ref "U93") (pin "VCC") (pinfunction "VCC_VCC") (pintype "unspecified"))
      (node (ref "U94") (pin "VCC") (pinfunction "VCC_VCC") (pintype "unspecified"))
      (node (ref "U95") (pin "VCC") (pinfunction "VCC_VCC") (pintype "unspecified"))
      (node (ref "U96") (pin "VCC") (pinfunction "VCC_VCC") (pintype "unspecified"))
      (node (ref "U97") (pin "VCC") (pinfunction "VCC_VCC") (pintype "unspecified"))
      (node (ref "U98") (pin "VCC") (pinfunction "VCC_VCC") (pintype "unspecified"))
      (node (ref "U99") (pin "VCC") (pinfunction "VCC_VCC") (pintype "unspecified"))
    )
    (net (code "2") (name "/COL_1") (class "Default")
      (node (ref "U1") (pin "1") (pinfunction "1_1") (pintype "unspecified"))
      (node (ref "U103") (pin "20") (pinfunction "GP15_20") (pintype "unspecified"))
      (node (ref "U11") (pin "1") (pinfunction "1_1") (pintype "unspecified"))
      (node (ref "U21") (pin "1") (pinfunction "1_1") (pintype "unspecified"))
      (node (ref "U31") (pin "1") (pinfunction "1_1") (pintype "unspecified"))
      (node (ref "U41") (pin "1") (pinfunction "1_1") (pintype "unspecified"))
      (node (ref "U51") (pin "1") (pinfunction "1_1") (pintype "unspecified"))
      (node (ref "U61") (pin "1") (pinfunction "1_1") (pintype "unspecified"))
      (node (ref "U71") (pin "1") (pinfunction "1_1") (pintype "unspecified"))
      (node (ref "U81") (pin "1") (pinfunction "1_1") (pintype "unspecified"))
    )
    (net (code "3") (name "/COL_2") (class "Default")
      (node (ref "U103") (pin "19") (pinfunction "GP14_19") (pintype "unspecified"))
      (node (ref "U12") (pin "1") (pinfunction "1_1") (pintype "unspecified"))
      (node (ref "U2") (pin "1") (pinfunction "1_1") (pintype "unspecified"))
      (node (ref "U22") (pin "1") (pinfunction "1_1") (pintype "unspecified"))
      (node (ref "U32") (pin "1") (pinfunction "1_1") (pintype "unspecified"))
      (node (ref "U42") (pin "1") (pinfunction "1_1") (pintype "unspecified"))
      (node (ref "U52") (pin "1") (pinfunction "1_1") (pintype "unspecified"))
      (node (ref "U62") (pin "1") (pinfunction "1_1") (pintype "unspecified"))
      (node (ref "U72") (pin "1") (pinfunction "1_1") (pintype "unspecified"))
      (node (ref "U82") (pin "1") (pinfunction "1_1") (pintype "unspecified"))
    )
    (net (code "4") (name "/COL_3") (class "Default")
      (node (ref "U103") (pin "17") (pinfunction "GP13_17") (pintype "unspecified"))
      (node (ref "U13") (pin "1") (pinfunction "1_1") (pintype "unspecified"))
      (node (ref "U23") (pin "1") (pinfunction "1_1") (pintype "unspecified"))
      (node (ref "U3") (pin "1") (pinfunction "1_1") (pintype "unspecified"))
      (node (ref "U33") (pin "1") (pinfunction "1_1") (pintype "unspecified"))
      (node (ref "U43") (pin "1") (pinfunction "1_1") (pintype "unspecified"))
      (node (ref "U53") (pin "1") (pinfunction "1_1") (pintype "unspecified"))
      (node (ref "U63") (pin "1") (pinfunction "1_1") (pintype "unspecified"))
      (node (ref "U73") (pin "1") (pinfunction "1_1") (pintype "unspecified"))
      (node (ref "U83") (pin "1") (pinfunction "1_1") (pintype "unspecified"))
    )
    (net (code "5") (name "/COL_4") (class "Default")
      (node (ref "U103") (pin "16") (pinfunction "GP12_16") (pintype "unspecified"))
      (node (ref "U14") (pin "1") (pinfunction "1_1") (pintype "unspecified"))
      (node (ref "U24") (pin "1") (pinfunction "1_1") (pintype "unspecified"))
      (node (ref "U34") (pin "1") (pinfunction "1_1") (pintype "unspecified"))
      (node (ref "U4") (pin "1") (pinfunction "1_1") (pintype "unspecified"))
      (node (ref "U44") (pin "1") (pinfunction "1_1") (pintype "unspecified"))
      (node (ref "U54") (pin "1") (pinfunction "1_1") (pintype "unspecified"))
      (node (ref "U64") (pin "1") (pinfunction "1_1") (pintype "unspecified"))
      (node (ref "U74") (pin "1") (pinfunction "1_1") (pintype "unspecified"))
      (node (ref "U84") (pin "1") (pinfunction "1_1") (pintype "unspecified"))
    )
    (net (code "6") (name "/COL_5") (class "Default")
      (node (ref "U103") (pin "15") (pinfunction "GP11_15") (pintype "unspecified"))
      (node (ref "U15") (pin "1") (pinfunction "1_1") (pintype "unspecified"))
      (node (ref "U25") (pin "1") (pinfunction "1_1") (pintype "unspecified"))
      (node (ref "U35") (pin "1") (pinfunction "1_1") (pintype "unspecified"))
      (node (ref "U45") (pin "1") (pinfunction "1_1") (pintype "unspecified"))
      (node (ref "U5") (pin "1") (pinfunction "1_1") (pintype "unspecified"))
      (node (ref "U55") (pin "1") (pinfunction "1_1") (pintype "unspecified"))
      (node (ref "U65") (pin "1") (pinfunction "1_1") (pintype "unspecified"))
      (node (ref "U75") (pin "1") (pinfunction "1_1") (pintype "unspecified"))
      (node (ref "U85") (pin "1") (pinfunction "1_1") (pintype "unspecified"))
    )
    (net (code "7") (name "/COL_6") (class "Default")
      (node (ref "U103") (pin "14") (pinfunction "GP10_14") (pintype "unspecified"))
      (node (ref "U16") (pin "1") (pinfunction "1_1") (pintype "unspecified"))
      (node (ref "U26") (pin "1") (pinfunction "1_1") (pintype "unspecified"))
      (node (ref "U36") (pin "1") (pinfunction "1_1") (pintype "unspecified"))
      (node (ref "U46") (pin "1") (pinfunction "1_1") (pintype "unspecified"))
      (node (ref "U56") (pin "1") (pinfunction "1_1") (pintype "unspecified"))
      (node (ref "U6") (pin "1") (pinfunction "1_1") (pintype "unspecified"))
      (node (ref "U66") (pin "1") (pinfunction "1_1") (pintype "unspecified"))
      (node (ref "U76") (pin "1") (pinfunction "1_1") (pintype "unspecified"))
      (node (ref "U86") (pin "1") (pinfunction "1_1") (pintype "unspecified"))
    )
    (net (code "8") (name "/COL_7") (class "Default")
      (node (ref "SW1") (pin "E") (pinfunction "E_E") (pintype "unspecified"))
      (node (ref "U103") (pin "12") (pinfunction "GP9_12") (pintype "unspecified"))
      (node (ref "U17") (pin "1") (pinfunction "1_1") (pintype "unspecified"))
      (node (ref "U27") (pin "1") (pinfunction "1_1") (pintype "unspecified"))
      (node (ref "U37") (pin "1") (pinfunction "1_1") (pintype "unspecified"))
      (node (ref "U47") (pin "1") (pinfunction "1_1") (pintype "unspecified"))
      (node (ref "U57") (pin "1") (pinfunction "1_1") (pintype "unspecified"))
      (node (ref "U67") (pin "1") (pinfunction "1_1") (pintype "unspecified"))
      (node (ref "U7") (pin "1") (pinfunction "1_1") (pintype "unspecified"))
      (node (ref "U77") (pin "1") (pinfunction "1_1") (pintype "unspecified"))
    )
    (net (code "9") (name "/COL_8") (class "Default")
      (node (ref "U103") (pin "11") (pinfunction "GP8_11") (pintype "unspecified"))
      (node (ref "U18") (pin "1") (pinfunction "1_1") (pintype "unspecified"))
      (node (ref "U28") (pin "1") (pinfunction "1_1") (pintype "unspecified"))
      (node (ref "U38") (pin "1") (pinfunction "1_1") (pintype "unspecified"))
      (node (ref "U48") (pin "1") (pinfunction "1_1") (pintype "unspecified"))
      (node (ref "U58") (pin "1") (pinfunction "1_1") (pintype "unspecified"))
      (node (ref "U68") (pin "1") (pinfunction "1_1") (pintype "unspecified"))
      (node (ref "U78") (pin "1") (pinfunction "1_1") (pintype "unspecified"))
      (node (ref "U8") (pin "1") (pinfunction "1_1") (pintype "unspecified"))
    )
    (net (code "10") (name "/COL_9") (class "Default")
      (node (ref "U103") (pin "10") (pinfunction "GP7_10") (pintype "unspecified"))
      (node (ref "U19") (pin "1") (pinfunction "1_1") (pintype "unspecified"))
      (node (ref "U29") (pin "1") (pinfunction "1_1") (pintype "unspecified"))
      (node (ref "U39") (pin "1") (pinfunction "1_1") (pintype "unspecified"))
      (node (ref "U49") (pin "1") (pinfunction "1_1") (pintype "unspecified"))
      (node (ref "U59") (pin "1") (pinfunction "1_1") (pintype "unspecified"))
      (node (ref "U69") (pin "1") (pinfunction "1_1") (pintype "unspecified"))
      (node (ref "U79") (pin "1") (pinfunction "1_1") (pintype "unspecified"))
      (node (ref "U9") (pin "1") (pinfunction "1_1") (pintype "unspecified"))
    )
    (net (code "11") (name "/COL_10") (class "Default")
      (node (ref "U10") (pin "1") (pinfunction "1_1") (pintype "unspecified"))
      (node (ref "U103") (pin "9") (pinfunction "GP6_9") (pintype "unspecified"))
      (node (ref "U20") (pin "1") (pinfunction "1_1") (pintype "unspecified"))
      (node (ref "U30") (pin "1") (pinfunction "1_1") (pintype "unspecified"))
      (node (ref "U40") (pin "1") (pinfunction "1_1") (pintype "unspecified"))
      (node (ref "U50") (pin "1") (pinfunction "1_1") (pintype "unspecified"))
      (node (ref "U60") (pin "1") (pinfunction "1_1") (pintype "unspecified"))
      (node (ref "U70") (pin "1") (pinfunction "1_1") (pintype "unspecified"))
      (node (ref "U80") (pin "1") (pinfunction "1_1") (pintype "unspecified"))
    )
    (net (code "12") (name "/EC_A") (class "Default")
      (node (ref "SW1") (pin "A") (pinfunction "A_A") (pintype "unspecified"))
      (node (ref "U103") (pin "2") (pinfunction "GP1_2") (pintype "unspecified"))
    )
    (net (code "13") (name "/EC_B") (class "Default")
      (node (ref "SW1") (pin "B") (pinfunction "B_B") (pintype "unspecified"))
      (node (ref "U103") (pin "1") (pinfunction "GP0_1") (pintype "unspecified"))
    )
    (net (code "14") (name "/GP2") (class "Default")
      (node (ref "U103") (pin "4") (pinfunction "GP2_4") (pintype "unspecified"))
      (node (ref "U104") (pin "6") (pinfunction "6_6") (pintype "unspecified"))
    )
    (net (code "15") (name "/GP3") (class "Default")
      (node (ref "U103") (pin "5") (pinfunction "GP3_5") (pintype "unspecified"))
      (node (ref "U104") (pin "5") (pinfunction "5_5") (pintype "unspecified"))
    )
    (net (code "16") (name "/GP4") (class "Default")
      (node (ref "U103") (pin "6") (pinfunction "GP4_6") (pintype "unspecified"))
      (node (ref "U104") (pin "4") (pinfunction "4_4") (pintype "unspecified"))
    )
    (net (code "17") (name "/GP5") (class "Default")
      (node (ref "U103") (pin "7") (pinfunction "GP5_7") (pintype "unspecified"))
      (node (ref "U104") (pin "3") (pinfunction "3_3") (pintype "unspecified"))
    )
    (net (code "18") (name "/GP29_CONF") (class "Default")
      (node (ref "H2") (pin "2") (pinfunction "2_2") (pintype "unspecified"))
      (node (ref "U104") (pin "2") (pinfunction "2_2") (pintype "unspecified"))
    )
    (net (code "19") (name "/RGB_I") (class "Default")
      (node (ref "U103") (pin "34") (pinfunction "ADC2/GP28_34") (pintype "unspecified"))
      (node (ref "U87") (pin "DIN") (pinfunction "DIN_DIN") (pintype "unspecified"))
    )
    (net (code "20") (name "/ROW_1") (class "Default")
      (node (ref "D1") (pin "1") (pinfunction "A_1") (pintype "unspecified"))
      (node (ref "D10") (pin "1") (pinfunction "A_1") (pintype "unspecified"))
      (node (ref "D2") (pin "1") (pinfunction "A_1") (pintype "unspecified"))
      (node (ref "D3") (pin "1") (pinfunction "A_1") (pintype "unspecified"))
      (node (ref "D4") (pin "1") (pinfunction "A_1") (pintype "unspecified"))
      (node (ref "D5") (pin "1") (pinfunction "A_1") (pintype "unspecified"))
      (node (ref "D6") (pin "1") (pinfunction "A_1") (pintype "unspecified"))
      (node (ref "D7") (pin "1") (pinfunction "A_1") (pintype "unspecified"))
      (node (ref "D8") (pin "1") (pinfunction "A_1") (pintype "unspecified"))
      (node (ref "D9") (pin "1") (pinfunction "A_1") (pintype "unspecified"))
      (node (ref "U103") (pin "32") (pinfunction "ADC1/GP27_32") (pintype "unspecified"))
    )
    (net (code "21") (name "/ROW_2") (class "Default")
      (node (ref "D11") (pin "1") (pinfunction "A_1") (pintype "unspecified"))
      (node (ref "D12") (pin "1") (pinfunction "A_1") (pintype "unspecified"))
      (node (ref "D13") (pin "1") (pinfunction "A_1") (pintype "unspecified"))
      (node (ref "D14") (pin "1") (pinfunction "A_1") (pintype "unspecified"))
      (node (ref "D15") (pin "1") (pinfunction "A_1") (pintype "unspecified"))
      (node (ref "D16") (pin "1") (pinfunction "A_1") (pintype "unspecified"))
      (node (ref "D17") (pin "1") (pinfunction "A_1") (pintype "unspecified"))
      (node (ref "D18") (pin "1") (pinfunction "A_1") (pintype "unspecified"))
      (node (ref "D19") (pin "1") (pinfunction "A_1") (pintype "unspecified"))
      (node (ref "D20") (pin "1") (pinfunction "A_1") (pintype "unspecified"))
      (node (ref "U103") (pin "31") (pinfunction "ADC0/GP26_31") (pintype "unspecified"))
    )
    (net (code "22") (name "/ROW_3") (class "Default")
      (node (ref "D21") (pin "1") (pinfunction "A_1") (pintype "unspecified"))
      (node (ref "D22") (pin "1") (pinfunction "A_1") (pintype "unspecified"))
      (node (ref "D23") (pin "1") (pinfunction "A_1") (pintype "unspecified"))
      (node (ref "D24") (pin "1") (pinfunction "A_1") (pintype "unspecified"))
      (node (ref "D25") (pin "1") (pinfunction "A_1") (pintype "unspecified"))
      (node (ref "D26") (pin "1") (pinfunction "A_1") (pintype "unspecified"))
      (node (ref "D27") (pin "1") (pinfunction "A_1") (pintype "unspecified"))
      (node (ref "D28") (pin "1") (pinfunction "A_1") (pintype "unspecified"))
      (node (ref "D29") (pin "1") (pinfunction "A_1") (pintype "unspecified"))
      (node (ref "D30") (pin "1") (pinfunction "A_1") (pintype "unspecified"))
      (node (ref "U103") (pin "29") (pinfunction "GP22_29") (pintype "unspecified"))
    )
    (net (code "23") (name "/ROW_4") (class "Default")
      (node (ref "D31") (pin "1") (pinfunction "A_1") (pintype "unspecified"))
      (node (ref "D32") (pin "1") (pinfunction "A_1") (pintype "unspecified"))
      (node (ref "D33") (pin "1") (pinfunction "A_1") (pintype "unspecified"))
      (node (ref "D34") (pin "1") (pinfunction "A_1") (pintype "unspecified"))
      (node (ref "D35") (pin "1") (pinfunction "A_1") (pintype "unspecified"))
      (node (ref "D36") (pin "1") (pinfunction "A_1") (pintype "unspecified"))
      (node (ref "D37") (pin "1") (pinfunction "A_1") (pintype "unspecified"))
      (node (ref "D38") (pin "1") (pinfunction "A_1") (pintype "unspecified"))
      (node (ref "D39") (pin "1") (pinfunction "A_1") (pintype "unspecified"))
      (node (ref "D40") (pin "1") (pinfunction "A_1") (pintype "unspecified"))
      (node (ref "U103") (pin "27") (pinfunction "GP21_27") (pintype "unspecified"))
    )
    (net (code "24") (name "/ROW_5") (class "Default")
      (node (ref "D41") (pin "1") (pinfunction "A_1") (pintype "unspecified"))
      (node (ref "D42") (pin "1") (pinfunction "A_1") (pintype "unspecified"))
      (node (ref "D43") (pin "1") (pinfunction "A_1") (pintype "unspecified"))
      (node (ref "D44") (pin "1") (pinfunction "A_1") (pintype "unspecified"))
      (node (ref "D45") (pin "1") (pinfunction "A_1") (pintype "unspecified"))
      (node (ref "D46") (pin "1") (pinfunction "A_1") (pintype "unspecified"))
      (node (ref "D47") (pin "1") (pinfunction "A_1") (pintype "unspecified"))
      (node (ref "D48") (pin "1") (pinfunction "A_1") (pintype "unspecified"))
      (node (ref "D49") (pin "1") (pinfunction "A_1") (pintype "unspecified"))
      (node (ref "D50") (pin "1") (pinfunction "A_1") (pintype "unspecified"))
      (node (ref "U103") (pin "26") (pinfunction "GP20_26") (pintype "unspecified"))
    )
    (net (code "25") (name "/ROW_6") (class "Default")
      (node (ref "D51") (pin "1") (pinfunction "A_1") (pintype "unspecified"))
      (node (ref "D52") (pin "1") (pinfunction "A_1") (pintype "unspecified"))
      (node (ref "D53") (pin "1") (pinfunction "A_1") (pintype "unspecified"))
      (node (ref "D54") (pin "1") (pinfunction "A_1") (pintype "unspecified"))
      (node (ref "D55") (pin "1") (pinfunction "A_1") (pintype "unspecified"))
      (node (ref "D56") (pin "1") (pinfunction "A_1") (pintype "unspecified"))
      (node (ref "D57") (pin "1") (pinfunction "A_1") (pintype "unspecified"))
      (node (ref "D58") (pin "1") (pinfunction "A_1") (pintype "unspecified"))
      (node (ref "D59") (pin "1") (pinfunction "A_1") (pintype "unspecified"))
      (node (ref "D60") (pin "1") (pinfunction "A_1") (pintype "unspecified"))
      (node (ref "U103") (pin "25") (pinfunction "GP19_25") (pintype "unspecified"))
    )
    (net (code "26") (name "/ROW_7") (class "Default")
      (node (ref "D61") (pin "1") (pinfunction "A_1") (pintype "unspecified"))
      (node (ref "D62") (pin "1") (pinfunction "A_1") (pintype "unspecified"))
      (node (ref "D63") (pin "1") (pinfunction "A_1") (pintype "unspecified"))
      (node (ref "D64") (pin "1") (pinfunction "A_1") (pintype "unspecified"))
      (node (ref "D65") (pin "1") (pinfunction "A_1") (pintype "unspecified"))
      (node (ref "D66") (pin "1") (pinfunction "A_1") (pintype "unspecified"))
      (node (ref "D67") (pin "1") (pinfunction "A_1") (pintype "unspecified"))
      (node (ref "D68") (pin "1") (pinfunction "A_1") (pintype "unspecified"))
      (node (ref "D69") (pin "1") (pinfunction "A_1") (pintype "unspecified"))
      (node (ref "D70") (pin "1") (pinfunction "A_1") (pintype "unspecified"))
      (node (ref "U103") (pin "24") (pinfunction "GP18_24") (pintype "unspecified"))
    )
    (net (code "27") (name "/ROW_8") (class "Default")
      (node (ref "D71") (pin "1") (pinfunction "A_1") (pintype "unspecified"))
      (node (ref "D72") (pin "1") (pinfunction "A_1") (pintype "unspecified"))
      (node (ref "D73") (pin "1") (pinfunction "A_1") (pintype "unspecified"))
      (node (ref "D74") (pin "1") (pinfunction "A_1") (pintype "unspecified"))
      (node (ref "D75") (pin "1") (pinfunction "A_1") (pintype "unspecified"))
      (node (ref "D76") (pin "1") (pinfunction "A_1") (pintype "unspecified"))
      (node (ref "D77") (pin "1") (pinfunction "A_1") (pintype "unspecified"))
      (node (ref "D78") (pin "1") (pinfunction "A_1") (pintype "unspecified"))
      (node (ref "D79") (pin "1") (pinfunction "A_1") (pintype "unspecified"))
      (node (ref "D80") (pin "1") (pinfunction "A_1") (pintype "unspecified"))
      (node (ref "U103") (pin "22") (pinfunction "GP17_22") (pintype "unspecified"))
    )
    (net (code "28") (name "/ROW_9") (class "Default")
      (node (ref "D81") (pin "1") (pinfunction "A_1") (pintype "unspecified"))
      (node (ref "D82") (pin "1") (pinfunction "A_1") (pintype "unspecified"))
      (node (ref "D83") (pin "1") (pinfunction "A_1") (pintype "unspecified"))
      (node (ref "D84") (pin "1") (pinfunction "A_1") (pintype "unspecified"))
      (node (ref "D85") (pin "1") (pinfunction "A_1") (pintype "unspecified"))
      (node (ref "D86") (pin "1") (pinfunction "A_1") (pintype "unspecified"))
      (node (ref "SW1") (pin "D") (pinfunction "D_D") (pintype "unspecified"))
      (node (ref "U103") (pin "21") (pinfunction "GP16_21") (pintype "unspecified"))
    )
    (net (code "29") (name "/YD_GP29") (class "Default")
      (node (ref "H2") (pin "3") (pinfunction "3_3") (pintype "unspecified"))
      (node (ref "U103") (pin "35") (pinfunction "ADC_VREF_35") (pintype "input"))
    )
    (net (code "30") (name "GND") (class "Default")
      (node (ref "H2") (pin "1") (pinfunction "1_1") (pintype "unspecified"))
      (node (ref "SW1") (pin "C") (pinfunction "C_C") (pintype "unspecified"))
      (node (ref "U100") (pin "GND") (pinfunction "GND_GND") (pintype "unspecified"))
      (node (ref "U101") (pin "GND") (pinfunction "GND_GND") (pintype "unspecified"))
      (node (ref "U102") (pin "GND") (pinfunction "GND_GND") (pintype "unspecified"))
      (node (ref "U103") (pin "13") (pinfunction "GND_13") (pintype "unspecified"))
      (node (ref "U103") (pin "18") (pinfunction "GND_18") (pintype "unspecified"))
      (node (ref "U103") (pin "23") (pinfunction "GND_23") (pintype "unspecified"))
      (node (ref "U103") (pin "28") (pinfunction "GND_28") (pintype "unspecified"))
      (node (ref "U103") (pin "3") (pinfunction "GND_3") (pintype "unspecified"))
      (node (ref "U103") (pin "33") (pinfunction "AGND/GND_33") (pintype "unspecified"))
      (node (ref "U103") (pin "38") (pinfunction "GND_38") (pintype "unspecified"))
      (node (ref "U103") (pin "8") (pinfunction "GND_8") (pintype "unspecified"))
      (node (ref "U104") (pin "8") (pinfunction "8_8") (pintype "unspecified"))
      (node (ref "U105") (pin "GND") (pinfunction "GND_GND") (pintype "unspecified"))
      (node (ref "U106") (pin "GND") (pinfunction "GND_GND") (pintype "unspecified"))
      (node (ref "U107") (pin "GND") (pinfunction "GND_GND") (pintype "unspecified"))
      (node (ref "U108") (pin "GND") (pinfunction "GND_GND") (pintype "unspecified"))
      (node (ref "U109") (pin "GND") (pinfunction "GND_GND") (pintype "unspecified"))
      (node (ref "U110") (pin "GND") (pinfunction "GND_GND") (pintype "unspecified"))
      (node (ref "U111") (pin "GND") (pinfunction "GND_GND") (pintype "unspecified"))
      (node (ref "U112") (pin "GND") (pinfunction "GND_GND") (pintype "unspecified"))
      (node (ref "U113") (pin "GND") (pinfunction "GND_GND") (pintype "unspecified"))
      (node (ref "U114") (pin "GND") (pinfunction "GND_GND") (pintype "unspecified"))
      (node (ref "U115") (pin "GND") (pinfunction "GND_GND") (pintype "unspecified"))
      (node (ref "U116") (pin "GND") (pinfunction "GND_GND") (pintype "unspecified"))
      (node (ref "U117") (pin "GND") (pinfunction "GND_GND") (pintype "unspecified"))
      (node (ref "U118") (pin "GND") (pinfunction "GND_GND") (pintype "unspecified"))
      (node (ref "U119") (pin "GND") (pinfunction "GND_GND") (pintype "unspecified"))
      (node (ref "U120") (pin "GND") (pinfunction "GND_GND") (pintype "unspecified"))
      (node (ref "U121") (pin "GND") (pinfunction "GND_GND") (pintype "unspecified"))
      (node (ref "U122") (pin "GND") (pinfunction "GND_GND") (pintype "unspecified"))
      (node (ref "U123") (pin "GND") (pinfunction "GND_GND") (pintype "unspecified"))
      (node (ref "U124") (pin "GND") (pinfunction "GND_GND") (pintype "unspecified"))
      (node (ref "U125") (pin "GND") (pinfunction "GND_GND") (pintype "unspecified"))
      (node (ref "U126") (pin "GND") (pinfunction "GND_GND") (pintype "unspecified"))
      (node (ref "U127") (pin "GND") (pinfunction "GND_GND") (pintype "unspecified"))
      (node (ref "U128") (pin "GND") (pinfunction "GND_GND") (pintype "unspecified"))
      (node (ref "U129") (pin "GND") (pinfunction "GND_GND") (pintype "unspecified"))
      (node (ref "U130") (pin "GND") (pinfunction "GND_GND") (pintype "unspecified"))
      (node (ref "U131") (pin "GND") (pinfunction "GND_GND") (pintype "unspecified"))
      (node (ref "U132") (pin "GND") (pinfunction "GND_GND") (pintype "unspecified"))
      (node (ref "U133") (pin "GND") (pinfunction "GND_GND") (pintype "unspecified"))
      (node (ref "U134") (pin "GND") (pinfunction "GND_GND") (pintype "unspecified"))
      (node (ref "U135") (pin "GND") (pinfunction "GND_GND") (pintype "unspecified"))
      (node (ref "U136") (pin "GND") (pinfunction "GND_GND") (pintype "unspecified"))
      (node (ref "U137") (pin "GND") (pinfunction "GND_GND") (pintype "unspecified"))
      (node (ref "U138") (pin "GND") (pinfunction "GND_GND") (pintype "unspecified"))
      (node (ref "U139") (pin "GND") (pinfunction "GND_GND") (pintype "unspecified"))
      (node (ref "U140") (pin "GND") (pinfunction "GND_GND") (pintype "unspecified"))
      (node (ref "U141") (pin "GND") (pinfunction "GND_GND") (pintype "unspecified"))
      (node (ref "U142") (pin "GND") (pinfunction "GND_GND") (pintype "unspecified"))
      (node (ref "U143") (pin "GND") (pinfunction "GND_GND") (pintype "unspecified"))
      (node (ref "U144") (pin "GND") (pinfunction "GND_GND") (pintype "unspecified"))
      (node (ref "U145") (pin "GND") (pinfunction "GND_GND") (pintype "unspecified"))
      (node (ref "U146") (pin "GND") (pinfunction "GND_GND") (pintype "unspecified"))
      (node (ref "U147") (pin "GND") (pinfunction "GND_GND") (pintype "unspecified"))
      (node (ref "U148") (pin "GND") (pinfunction "GND_GND") (pintype "unspecified"))
      (node (ref "U149") (pin "GND") (pinfunction "GND_GND") (pintype "unspecified"))
      (node (ref "U150") (pin "GND") (pinfunction "GND_GND") (pintype "unspecified"))
      (node (ref "U151") (pin "GND") (pinfunction "GND_GND") (pintype "unspecified"))
      (node (ref "U152") (pin "GND") (pinfunction "GND_GND") (pintype "unspecified"))
      (node (ref "U153") (pin "GND") (pinfunction "GND_GND") (pintype "unspecified"))
      (node (ref "U154") (pin "GND") (pinfunction "GND_GND") (pintype "unspecified"))
      (node (ref "U155") (pin "GND") (pinfunction "GND_GND") (pintype "unspecified"))
      (node (ref "U156") (pin "GND") (pinfunction "GND_GND") (pintype "unspecified"))
      (node (ref "U157") (pin "GND") (pinfunction "GND_GND") (pintype "unspecified"))
      (node (ref "U158") (pin "GND") (pinfunction "GND_GND") (pintype "unspecified"))
      (node (ref "U159") (pin "GND") (pinfunction "GND_GND") (pintype "unspecified"))
      (node (ref "U160") (pin "GND") (pinfunction "GND_GND") (pintype "unspecified"))
      (node (ref "U161") (pin "GND") (pinfunction "GND_GND") (pintype "unspecified"))
      (node (ref "U162") (pin "GND") (pinfunction "GND_GND") (pintype "unspecified"))
      (node (ref "U163") (pin "GND") (pinfunction "GND_GND") (pintype "unspecified"))
      (node (ref "U164") (pin "GND") (pinfunction "GND_GND") (pintype "unspecified"))
      (node (ref "U165") (pin "GND") (pinfunction "GND_GND") (pintype "unspecified"))
      (node (ref "U166") (pin "GND") (pinfunction "GND_GND") (pintype "unspecified"))
      (node (ref "U167") (pin "GND") (pinfunction "GND_GND") (pintype "unspecified"))
      (node (ref "U168") (pin "GND") (pinfunction "GND_GND") (pintype "unspecified"))
      (node (ref "U177") (pin "GND") (pinfunction "GND_GND") (pintype "unspecified"))
      (node (ref "U178") (pin "GND") (pinfunction "GND_GND") (pintype "unspecified"))
      (node (ref "U181") (pin "GND") (pinfunction "GND_GND") (pintype "unspecified"))
      (node (ref "U182") (pin "GND") (pinfunction "GND_GND") (pintype "unspecified"))
      (node (ref "U183") (pin "GND") (pinfunction "GND_GND") (pintype "unspecified"))
      (node (ref "U184") (pin "GND") (pinfunction "GND_GND") (pintype "unspecified"))
      (node (ref "U87") (pin "GND") (pinfunction "GND_GND") (pintype "unspecified"))
      (node (ref "U88") (pin "GND") (pinfunction "GND_GND") (pintype "unspecified"))
      (node (ref "U89") (pin "GND") (pinfunction "GND_GND") (pintype "unspecified"))
      (node (ref "U90") (pin "GND") (pinfunction "GND_GND") (pintype "unspecified"))
      (node (ref "U91") (pin "GND") (pinfunction "GND_GND") (pintype "unspecified"))
      (node (ref "U92") (pin "GND") (pinfunction "GND_GND") (pintype "unspecified"))
      (node (ref "U93") (pin "GND") (pinfunction "GND_GND") (pintype "unspecified"))
      (node (ref "U94") (pin "GND") (pinfunction "GND_GND") (pintype "unspecified"))
      (node (ref "U95") (pin "GND") (pinfunction "GND_GND") (pintype "unspecified"))
      (node (ref "U96") (pin "GND") (pinfunction "GND_GND") (pintype "unspecified"))
      (node (ref "U97") (pin "GND") (pinfunction "GND_GND") (pintype "unspecified"))
      (node (ref "U98") (pin "GND") (pinfunction "GND_GND") (pintype "unspecified"))
      (node (ref "U99") (pin "GND") (pinfunction "GND_GND") (pintype "unspecified"))
    )
    (net (code "31") (name "Net-(D1-K)") (class "Default")
      (node (ref "D1") (pin "2") (pinfunction "K_2") (pintype "unspecified"))
      (node (ref "U1") (pin "2") (pinfunction "2_2") (pintype "unspecified"))
    )
    (net (code "32") (name "Net-(D2-K)") (class "Default")
      (node (ref "D2") (pin "2") (pinfunction "K_2") (pintype "unspecified"))
      (node (ref "U2") (pin "2") (pinfunction "2_2") (pintype "unspecified"))
    )
    (net (code "33") (name "Net-(D3-K)") (class "Default")
      (node (ref "D3") (pin "2") (pinfunction "K_2") (pintype "unspecified"))
      (node (ref "U3") (pin "2") (pinfunction "2_2") (pintype "unspecified"))
    )
    (net (code "34") (name "Net-(D4-K)") (class "Default")
      (node (ref "D4") (pin "2") (pinfunction "K_2") (pintype "unspecified"))
      (node (ref "U4") (pin "2") (pinfunction "2_2") (pintype "unspecified"))
    )
    (net (code "35") (name "Net-(D5-K)") (class "Default")
      (node (ref "D5") (pin "2") (pinfunction "K_2") (pintype "unspecified"))
      (node (ref "U5") (pin "2") (pinfunction "2_2") (pintype "unspecified"))
    )
    (net (code "36") (name "Net-(D6-K)") (class "Default")
      (node (ref "D6") (pin "2") (pinfunction "K_2") (pintype "unspecified"))
      (node (ref "U6") (pin "2") (pinfunction "2_2") (pintype "unspecified"))
    )
    (net (code "37") (name "Net-(D7-K)") (class "Default")
      (node (ref "D7") (pin "2") (pinfunction "K_2") (pintype "unspecified"))
      (node (ref "U7") (pin "2") (pinfunction "2_2") (pintype "unspecified"))
    )
    (net (code "38") (name "Net-(D8-K)") (class "Default")
      (node (ref "D8") (pin "2") (pinfunction "K_2") (pintype "unspecified"))
      (node (ref "U8") (pin "2") (pinfunction "2_2") (pintype "unspecified"))
    )
    (net (code "39") (name "Net-(D9-K)") (class "Default")
      (node (ref "D9") (pin "2") (pinfunction "K_2") (pintype "unspecified"))
      (node (ref "U9") (pin "2") (pinfunction "2_2") (pintype "unspecified"))
    )
    (net (code "40") (name "Net-(D10-K)") (class "Default")
      (node (ref "D10") (pin "2") (pinfunction "K_2") (pintype "unspecified"))
      (node (ref "U10") (pin "2") (pinfunction "2_2") (pintype "unspecified"))
    )
    (net (code "41") (name "Net-(D11-K)") (class "Default")
      (node (ref "D11") (pin "2") (pinfunction "K_2") (pintype "unspecified"))
      (node (ref "U11") (pin "2") (pinfunction "2_2") (pintype "unspecified"))
    )
    (net (code "42") (name "Net-(D12-K)") (class "Default")
      (node (ref "D12") (pin "2") (pinfunction "K_2") (pintype "unspecified"))
      (node (ref "U12") (pin "2") (pinfunction "2_2") (pintype "unspecified"))
    )
    (net (code "43") (name "Net-(D13-K)") (class "Default")
      (node (ref "D13") (pin "2") (pinfunction "K_2") (pintype "unspecified"))
      (node (ref "U13") (pin "2") (pinfunction "2_2") (pintype "unspecified"))
    )
    (net (code "44") (name "Net-(D14-K)") (class "Default")
      (node (ref "D14") (pin "2") (pinfunction "K_2") (pintype "unspecified"))
      (node (ref "U14") (pin "2") (pinfunction "2_2") (pintype "unspecified"))
    )
    (net (code "45") (name "Net-(D15-K)") (class "Default")
      (node (ref "D15") (pin "2") (pinfunction "K_2") (pintype "unspecified"))
      (node (ref "U15") (pin "2") (pinfunction "2_2") (pintype "unspecified"))
    )
    (net (code "46") (name "Net-(D16-K)") (class "Default")
      (node (ref "D16") (pin "2") (pinfunction "K_2") (pintype "unspecified"))
      (node (ref "U16") (pin "2") (pinfunction "2_2") (pintype "unspecified"))
    )
    (net (code "47") (name "Net-(D17-K)") (class "Default")
      (node (ref "D17") (pin "2") (pinfunction "K_2") (pintype "unspecified"))
      (node (ref "U17") (pin "2") (pinfunction "2_2") (pintype "unspecified"))
    )
    (net (code "48") (name "Net-(D18-K)") (class "Default")
      (node (ref "D18") (pin "2") (pinfunction "K_2") (pintype "unspecified"))
      (node (ref "U18") (pin "2") (pinfunction "2_2") (pintype "unspecified"))
    )
    (net (code "49") (name "Net-(D19-K)") (class "Default")
      (node (ref "D19") (pin "2") (pinfunction "K_2") (pintype "unspecified"))
      (node (ref "U19") (pin "2") (pinfunction "2_2") (pintype "unspecified"))
    )
    (net (code "50") (name "Net-(D20-K)") (class "Default")
      (node (ref "D20") (pin "2") (pinfunction "K_2") (pintype "unspecified"))
      (node (ref "U20") (pin "2") (pinfunction "2_2") (pintype "unspecified"))
    )
    (net (code "51") (name "Net-(D21-K)") (class "Default")
      (node (ref "D21") (pin "2") (pinfunction "K_2") (pintype "unspecified"))
      (node (ref "U21") (pin "2") (pinfunction "2_2") (pintype "unspecified"))
    )
    (net (code "52") (name "Net-(D22-K)") (class "Default")
      (node (ref "D22") (pin "2") (pinfunction "K_2") (pintype "unspecified"))
      (node (ref "U22") (pin "2") (pinfunction "2_2") (pintype "unspecified"))
    )
    (net (code "53") (name "Net-(D23-K)") (class "Default")
      (node (ref "D23") (pin "2") (pinfunction "K_2") (pintype "unspecified"))
      (node (ref "U23") (pin "2") (pinfunction "2_2") (pintype "unspecified"))
    )
    (net (code "54") (name "Net-(D24-K)") (class "Default")
      (node (ref "D24") (pin "2") (pinfunction "K_2") (pintype "unspecified"))
      (node (ref "U24") (pin "2") (pinfunction "2_2") (pintype "unspecified"))
    )
    (net (code "55") (name "Net-(D25-K)") (class "Default")
      (node (ref "D25") (pin "2") (pinfunction "K_2") (pintype "unspecified"))
      (node (ref "U25") (pin "2") (pinfunction "2_2") (pintype "unspecified"))
    )
    (net (code "56") (name "Net-(D26-K)") (class "Default")
      (node (ref "D26") (pin "2") (pinfunction "K_2") (pintype "unspecified"))
      (node (ref "U26") (pin "2") (pinfunction "2_2") (pintype "unspecified"))
    )
    (net (code "57") (name "Net-(D27-K)") (class "Default")
      (node (ref "D27") (pin "2") (pinfunction "K_2") (pintype "unspecified"))
      (node (ref "U27") (pin "2") (pinfunction "2_2") (pintype "unspecified"))
    )
    (net (code "58") (name "Net-(D28-K)") (class "Default")
      (node (ref "D28") (pin "2") (pinfunction "K_2") (pintype "unspecified"))
      (node (ref "U28") (pin "2") (pinfunction "2_2") (pintype "unspecified"))
    )
    (net (code "59") (name "Net-(D29-K)") (class "Default")
      (node (ref "D29") (pin "2") (pinfunction "K_2") (pintype "unspecified"))
      (node (ref "U29") (pin "2") (pinfunction "2_2") (pintype "unspecified"))
    )
    (net (code "60") (name "Net-(D30-K)") (class "Default")
      (node (ref "D30") (pin "2") (pinfunction "K_2") (pintype "unspecified"))
      (node (ref "U30") (pin "2") (pinfunction "2_2") (pintype "unspecified"))
    )
    (net (code "61") (name "Net-(D31-K)") (class "Default")
      (node (ref "D31") (pin "2") (pinfunction "K_2") (pintype "unspecified"))
      (node (ref "U31") (pin "2") (pinfunction "2_2") (pintype "unspecified"))
    )
    (net (code "62") (name "Net-(D32-K)") (class "Default")
      (node (ref "D32") (pin "2") (pinfunction "K_2") (pintype "unspecified"))
      (node (ref "U32") (pin "2") (pinfunction "2_2") (pintype "unspecified"))
    )
    (net (code "63") (name "Net-(D33-K)") (class "Default")
      (node (ref "D33") (pin "2") (pinfunction "K_2") (pintype "unspecified"))
      (node (ref "U33") (pin "2") (pinfunction "2_2") (pintype "unspecified"))
    )
    (net (code "64") (name "Net-(D34-K)") (class "Default")
      (node (ref "D34") (pin "2") (pinfunction "K_2") (pintype "unspecified"))
      (node (ref "U34") (pin "2") (pinfunction "2_2") (pintype "unspecified"))
    )
    (net (code "65") (name "Net-(D35-K)") (class "Default")
      (node (ref "D35") (pin "2") (pinfunction "K_2") (pintype "unspecified"))
      (node (ref "U35") (pin "2") (pinfunction "2_2") (pintype "unspecified"))
    )
    (net (code "66") (name "Net-(D36-K)") (class "Default")
      (node (ref "D36") (pin "2") (pinfunction "K_2") (pintype "unspecified"))
      (node (ref "U36") (pin "2") (pinfunction "2_2") (pintype "unspecified"))
    )
    (net (code "67") (name "Net-(D37-K)") (class "Default")
      (node (ref "D37") (pin "2") (pinfunction "K_2") (pintype "unspecified"))
      (node (ref "U37") (pin "2") (pinfunction "2_2") (pintype "unspecified"))
    )
    (net (code "68") (name "Net-(D38-K)") (class "Default")
      (node (ref "D38") (pin "2") (pinfunction "K_2") (pintype "unspecified"))
      (node (ref "U38") (pin "2") (pinfunction "2_2") (pintype "unspecified"))
    )
    (net (code "69") (name "Net-(D39-K)") (class "Default")
      (node (ref "D39") (pin "2") (pinfunction "K_2") (pintype "unspecified"))
      (node (ref "U39") (pin "2") (pinfunction "2_2") (pintype "unspecified"))
    )
    (net (code "70") (name "Net-(D40-K)") (class "Default")
      (node (ref "D40") (pin "2") (pinfunction "K_2") (pintype "unspecified"))
      (node (ref "U40") (pin "2") (pinfunction "2_2") (pintype "unspecified"))
    )
    (net (code "71") (name "Net-(D41-K)") (class "Default")
      (node (ref "D41") (pin "2") (pinfunction "K_2") (pintype "unspecified"))
      (node (ref "U41") (pin "2") (pinfunction "2_2") (pintype "unspecified"))
    )
    (net (code "72") (name "Net-(D42-K)") (class "Default")
      (node (ref "D42") (pin "2") (pinfunction "K_2") (pintype "unspecified"))
      (node (ref "U42") (pin "2") (pinfunction "2_2") (pintype "unspecified"))
    )
    (net (code "73") (name "Net-(D43-K)") (class "Default")
      (node (ref "D43") (pin "2") (pinfunction "K_2") (pintype "unspecified"))
      (node (ref "U43") (pin "2") (pinfunction "2_2") (pintype "unspecified"))
    )
    (net (code "74") (name "Net-(D44-K)") (class "Default")
      (node (ref "D44") (pin "2") (pinfunction "K_2") (pintype "unspecified"))
      (node (ref "U44") (pin "2") (pinfunction "2_2") (pintype "unspecified"))
    )
    (net (code "75") (name "Net-(D45-K)") (class "Default")
      (node (ref "D45") (pin "2") (pinfunction "K_2") (pintype "unspecified"))
      (node (ref "U45") (pin "2") (pinfunction "2_2") (pintype "unspecified"))
    )
    (net (code "76") (name "Net-(D46-K)") (class "Default")
      (node (ref "D46") (pin "2") (pinfunction "K_2") (pintype "unspecified"))
      (node (ref "U46") (pin "2") (pinfunction "2_2") (pintype "unspecified"))
    )
    (net (code "77") (name "Net-(D47-K)") (class "Default")
      (node (ref "D47") (pin "2") (pinfunction "K_2") (pintype "unspecified"))
      (node (ref "U47") (pin "2") (pinfunction "2_2") (pintype "unspecified"))
    )
    (net (code "78") (name "Net-(D48-K)") (class "Default")
      (node (ref "D48") (pin "2") (pinfunction "K_2") (pintype "unspecified"))
      (node (ref "U48") (pin "2") (pinfunction "2_2") (pintype "unspecified"))
    )
    (net (code "79") (name "Net-(D49-K)") (class "Default")
      (node (ref "D49") (pin "2") (pinfunction "K_2") (pintype "unspecified"))
      (node (ref "U49") (pin "2") (pinfunction "2_2") (pintype "unspecified"))
    )
    (net (code "80") (name "Net-(D50-K)") (class "Default")
      (node (ref "D50") (pin "2") (pinfunction "K_2") (pintype "unspecified"))
      (node (ref "U50") (pin "2") (pinfunction "2_2") (pintype "unspecified"))
    )
    (net (code "81") (name "Net-(D51-K)") (class "Default")
      (node (ref "D51") (pin "2") (pinfunction "K_2") (pintype "unspecified"))
      (node (ref "U51") (pin "2") (pinfunction "2_2") (pintype "unspecified"))
    )
    (net (code "82") (name "Net-(D52-K)") (class "Default")
      (node (ref "D52") (pin "2") (pinfunction "K_2") (pintype "unspecified"))
      (node (ref "U52") (pin "2") (pinfunction "2_2") (pintype "unspecified"))
    )
    (net (code "83") (name "Net-(D53-K)") (class "Default")
      (node (ref "D53") (pin "2") (pinfunction "K_2") (pintype "unspecified"))
      (node (ref "U53") (pin "2") (pinfunction "2_2") (pintype "unspecified"))
    )
    (net (code "84") (name "Net-(D54-K)") (class "Default")
      (node (ref "D54") (pin "2") (pinfunction "K_2") (pintype "unspecified"))
      (node (ref "U54") (pin "2") (pinfunction "2_2") (pintype "unspecified"))
    )
    (net (code "85") (name "Net-(D55-K)") (class "Default")
      (node (ref "D55") (pin "2") (pinfunction "K_2") (pintype "unspecified"))
      (node (ref "U55") (pin "2") (pinfunction "2_2") (pintype "unspecified"))
    )
    (net (code "86") (name "Net-(D56-K)") (class "Default")
      (node (ref "D56") (pin "2") (pinfunction "K_2") (pintype "unspecified"))
      (node (ref "U56") (pin "2") (pinfunction "2_2") (pintype "unspecified"))
    )
    (net (code "87") (name "Net-(D57-K)") (class "Default")
      (node (ref "D57") (pin "2") (pinfunction "K_2") (pintype "unspecified"))
      (node (ref "U57") (pin "2") (pinfunction "2_2") (pintype "unspecified"))
    )
    (net (code "88") (name "Net-(D58-K)") (class "Default")
      (node (ref "D58") (pin "2") (pinfunction "K_2") (pintype "unspecified"))
      (node (ref "U58") (pin "2") (pinfunction "2_2") (pintype "unspecified"))
    )
    (net (code "89") (name "Net-(D59-K)") (class "Default")
      (node (ref "D59") (pin "2") (pinfunction "K_2") (pintype "unspecified"))
      (node (ref "U59") (pin "2") (pinfunction "2_2") (pintype "unspecified"))
    )
    (net (code "90") (name "Net-(D60-K)") (class "Default")
      (node (ref "D60") (pin "2") (pinfunction "K_2") (pintype "unspecified"))
      (node (ref "U60") (pin "2") (pinfunction "2_2") (pintype "unspecified"))
    )
    (net (code "91") (name "Net-(D61-K)") (class "Default")
      (node (ref "D61") (pin "2") (pinfunction "K_2") (pintype "unspecified"))
      (node (ref "U61") (pin "2") (pinfunction "2_2") (pintype "unspecified"))
    )
    (net (code "92") (name "Net-(D62-K)") (class "Default")
      (node (ref "D62") (pin "2") (pinfunction "K_2") (pintype "unspecified"))
      (node (ref "U62") (pin "2") (pinfunction "2_2") (pintype "unspecified"))
    )
    (net (code "93") (name "Net-(D63-K)") (class "Default")
      (node (ref "D63") (pin "2") (pinfunction "K_2") (pintype "unspecified"))
      (node (ref "U63") (pin "2") (pinfunction "2_2") (pintype "unspecified"))
    )
    (net (code "94") (name "Net-(D64-K)") (class "Default")
      (node (ref "D64") (pin "2") (pinfunction "K_2") (pintype "unspecified"))
      (node (ref "U64") (pin "2") (pinfunction "2_2") (pintype "unspecified"))
    )
    (net (code "95") (name "Net-(D65-K)") (class "Default")
      (node (ref "D65") (pin "2") (pinfunction "K_2") (pintype "unspecified"))
      (node (ref "U65") (pin "2") (pinfunction "2_2") (pintype "unspecified"))
    )
    (net (code "96") (name "Net-(D66-K)") (class "Default")
      (node (ref "D66") (pin "2") (pinfunction "K_2") (pintype "unspecified"))
      (node (ref "U66") (pin "2") (pinfunction "2_2") (pintype "unspecified"))
    )
    (net (code "97") (name "Net-(D67-K)") (class "Default")
      (node (ref "D67") (pin "2") (pinfunction "K_2") (pintype "unspecified"))
      (node (ref "U67") (pin "2") (pinfunction "2_2") (pintype "unspecified"))
    )
    (net (code "98") (name "Net-(D68-K)") (class "Default")
      (node (ref "D68") (pin "2") (pinfunction "K_2") (pintype "unspecified"))
      (node (ref "U68") (pin "2") (pinfunction "2_2") (pintype "unspecified"))
    )
    (net (code "99") (name "Net-(D69-K)") (class "Default")
      (node (ref "D69") (pin "2") (pinfunction "K_2") (pintype "unspecified"))
      (node (ref "U69") (pin "2") (pinfunction "2_2") (pintype "unspecified"))
    )
    (net (code "100") (name "Net-(D70-K)") (class "Default")
      (node (ref "D70") (pin "2") (pinfunction "K_2") (pintype "unspecified"))
      (node (ref "U70") (pin "2") (pinfunction "2_2") (pintype "unspecified"))
    )
    (net (code "101") (name "Net-(D71-K)") (class "Default")
      (node (ref "D71") (pin "2") (pinfunction "K_2") (pintype "unspecified"))
      (node (ref "U71") (pin "2") (pinfunction "2_2") (pintype "unspecified"))
    )
    (net (code "102") (name "Net-(D72-K)") (class "Default")
      (node (ref "D72") (pin "2") (pinfunction "K_2") (pintype "unspecified"))
      (node (ref "U72") (pin "2") (pinfunction "2_2") (pintype "unspecified"))
    )
    (net (code "103") (name "Net-(D73-K)") (class "Default")
      (node (ref "D73") (pin "2") (pinfunction "K_2") (pintype "unspecified"))
      (node (ref "U73") (pin "2") (pinfunction "2_2") (pintype "unspecified"))
    )
    (net (code "104") (name "Net-(D74-K)") (class "Default")
      (node (ref "D74") (pin "2") (pinfunction "K_2") (pintype "unspecified"))
      (node (ref "U74") (pin "2") (pinfunction "2_2") (pintype "unspecified"))
    )
    (net (code "105") (name "Net-(D75-K)") (class "Default")
      (node (ref "D75") (pin "2") (pinfunction "K_2") (pintype "unspecified"))
      (node (ref "U75") (pin "2") (pinfunction "2_2") (pintype "unspecified"))
    )
    (net (code "106") (name "Net-(D76-K)") (class "Default")
      (node (ref "D76") (pin "2") (pinfunction "K_2") (pintype "unspecified"))
      (node (ref "U76") (pin "2") (pinfunction "2_2") (pintype "unspecified"))
    )
    (net (code "107") (name "Net-(D77-K)") (class "Default")
      (node (ref "D77") (pin "2") (pinfunction "K_2") (pintype "unspecified"))
      (node (ref "U77") (pin "2") (pinfunction "2_2") (pintype "unspecified"))
    )
    (net (code "108") (name "Net-(D78-K)") (class "Default")
      (node (ref "D78") (pin "2") (pinfunction "K_2") (pintype "unspecified"))
      (node (ref "U78") (pin "2") (pinfunction "2_2") (pintype "unspecified"))
    )
    (net (code "109") (name "Net-(D79-K)") (class "Default")
      (node (ref "D79") (pin "2") (pinfunction "K_2") (pintype "unspecified"))
      (node (ref "U79") (pin "2") (pinfunction "2_2") (pintype "unspecified"))
    )
    (net (code "110") (name "Net-(D80-K)") (class "Default")
      (node (ref "D80") (pin "2") (pinfunction "K_2") (pintype "unspecified"))
      (node (ref "U80") (pin "2") (pinfunction "2_2") (pintype "unspecified"))
    )
    (net (code "111") (name "Net-(D81-K)") (class "Default")
      (node (ref "D81") (pin "2") (pinfunction "K_2") (pintype "unspecified"))
      (node (ref "U81") (pin "2") (pinfunction "2_2") (pintype "unspecified"))
    )
    (net (code "112") (name "Net-(D82-K)") (class "Default")
      (node (ref "D82") (pin "2") (pinfunction "K_2") (pintype "unspecified"))
      (node (ref "U82") (pin "2") (pinfunction "2_2") (pintype "unspecified"))
    )
    (net (code "113") (name "Net-(D83-K)") (class "Default")
      (node (ref "D83") (pin "2") (pinfunction "K_2") (pintype "unspecified"))
      (node (ref "U83") (pin "2") (pinfunction "2_2") (pintype "unspecified"))
    )
    (net (code "114") (name "Net-(D84-K)") (class "Default")
      (node (ref "D84") (pin "2") (pinfunction "K_2") (pintype "unspecified"))
      (node (ref "U84") (pin "2") (pinfunction "2_2") (pintype "unspecified"))
    )
    (net (code "115") (name "Net-(D85-K)") (class "Default")
      (node (ref "D85") (pin "2") (pinfunction "K_2") (pintype "unspecified"))
      (node (ref "U85") (pin "2") (pinfunction "2_2") (pintype "unspecified"))
    )
    (net (code "116") (name "Net-(D86-K)") (class "Default")
      (node (ref "D86") (pin "2") (pinfunction "K_2") (pintype "unspecified"))
      (node (ref "U86") (pin "2") (pinfunction "2_2") (pintype "unspecified"))
    )
    (net (code "117") (name "Net-(U87-PadOUT)") (class "Default")
      (node (ref "U87") (pin "OUT") (pinfunction "OUT_OUT") (pintype "unspecified"))
      (node (ref "U88") (pin "DIN") (pinfunction "DIN_DIN") (pintype "unspecified"))
    )
    (net (code "118") (name "Net-(U88-PadOUT)") (class "Default")
      (node (ref "U88") (pin "OUT") (pinfunction "OUT_OUT") (pintype "unspecified"))
      (node (ref "U89") (pin "DIN") (pinfunction "DIN_DIN") (pintype "unspecified"))
    )
    (net (code "119") (name "Net-(U89-PadOUT)") (class "Default")
      (node (ref "U89") (pin "OUT") (pinfunction "OUT_OUT") (pintype "unspecified"))
      (node (ref "U90") (pin "DIN") (pinfunction "DIN_DIN") (pintype "unspecified"))
    )
    (net (code "120") (name "Net-(U90-PadOUT)") (class "Default")
      (node (ref "U90") (pin "OUT") (pinfunction "OUT_OUT") (pintype "unspecified"))
      (node (ref "U91") (pin "DIN") (pinfunction "DIN_DIN") (pintype "unspecified"))
    )
    (net (code "121") (name "Net-(U91-PadOUT)") (class "Default")
      (node (ref "U91") (pin "OUT") (pinfunction "OUT_OUT") (pintype "unspecified"))
      (node (ref "U92") (pin "DIN") (pinfunction "DIN_DIN") (pintype "unspecified"))
    )
    (net (code "122") (name "Net-(U92-PadOUT)") (class "Default")
      (node (ref "U92") (pin "OUT") (pinfunction "OUT_OUT") (pintype "unspecified"))
      (node (ref "U93") (pin "DIN") (pinfunction "DIN_DIN") (pintype "unspecified"))
    )
    (net (code "123") (name "Net-(U93-PadOUT)") (class "Default")
      (node (ref "U93") (pin "OUT") (pinfunction "OUT_OUT") (pintype "unspecified"))
      (node (ref "U94") (pin "DIN") (pinfunction "DIN_DIN") (pintype "unspecified"))
    )
    (net (code "124") (name "Net-(U94-PadOUT)") (class "Default")
      (node (ref "U94") (pin "OUT") (pinfunction "OUT_OUT") (pintype "unspecified"))
      (node (ref "U95") (pin "DIN") (pinfunction "DIN_DIN") (pintype "unspecified"))
    )
    (net (code "125") (name "Net-(U95-PadOUT)") (class "Default")
      (node (ref "U95") (pin "OUT") (pinfunction "OUT_OUT") (pintype "unspecified"))
      (node (ref "U96") (pin "DIN") (pinfunction "DIN_DIN") (pintype "unspecified"))
    )
    (net (code "126") (name "Net-(U96-PadOUT)") (class "Default")
      (node (ref "U96") (pin "OUT") (pinfunction "OUT_OUT") (pintype "unspecified"))
      (node (ref "U97") (pin "DIN") (pinfunction "DIN_DIN") (pintype "unspecified"))
    )
    (net (code "127") (name "Net-(U97-PadOUT)") (class "Default")
      (node (ref "U97") (pin "OUT") (pinfunction "OUT_OUT") (pintype "unspecified"))
      (node (ref "U98") (pin "DIN") (pinfunction "DIN_DIN") (pintype "unspecified"))
    )
    (net (code "128") (name "Net-(U98-PadOUT)") (class "Default")
      (node (ref "U98") (pin "OUT") (pinfunction "OUT_OUT") (pintype "unspecified"))
      (node (ref "U99") (pin "DIN") (pinfunction "DIN_DIN") (pintype "unspecified"))
    )
    (net (code "129") (name "Net-(U100-PadDIN)") (class "Default")
      (node (ref "U100") (pin "DIN") (pinfunction "DIN_DIN") (pintype "unspecified"))
      (node (ref "U99") (pin "OUT") (pinfunction "OUT_OUT") (pintype "unspecified"))
    )
    (net (code "130") (name "Net-(U100-PadOUT)") (class "Default")
      (node (ref "U100") (pin "OUT") (pinfunction "OUT_OUT") (pintype "unspecified"))
      (node (ref "U101") (pin "DIN") (pinfunction "DIN_DIN") (pintype "unspecified"))
    )
    (net (code "131") (name "Net-(U101-PadOUT)") (class "Default")
      (node (ref "U101") (pin "OUT") (pinfunction "OUT_OUT") (pintype "unspecified"))
      (node (ref "U102") (pin "DIN") (pinfunction "DIN_DIN") (pintype "unspecified"))
    )
    (net (code "132") (name "Net-(U102-PadOUT)") (class "Default")
      (node (ref "U102") (pin "OUT") (pinfunction "OUT_OUT") (pintype "unspecified"))
      (node (ref "U120") (pin "DIN") (pinfunction "DIN_DIN") (pintype "unspecified"))
    )
    (net (code "133") (name "Net-(U105-PadDIN)") (class "Default")
      (node (ref "U105") (pin "DIN") (pinfunction "DIN_DIN") (pintype "unspecified"))
      (node (ref "U115") (pin "OUT") (pinfunction "OUT_OUT") (pintype "unspecified"))
    )
    (net (code "134") (name "Net-(U105-PadOUT)") (class "Default")
      (node (ref "U105") (pin "OUT") (pinfunction "OUT_OUT") (pintype "unspecified"))
      (node (ref "U106") (pin "DIN") (pinfunction "DIN_DIN") (pintype "unspecified"))
    )
    (net (code "135") (name "Net-(U106-PadOUT)") (class "Default")
      (node (ref "U106") (pin "OUT") (pinfunction "OUT_OUT") (pintype "unspecified"))
      (node (ref "U108") (pin "DIN") (pinfunction "DIN_DIN") (pintype "unspecified"))
    )
    (net (code "136") (name "Net-(U107-PadDIN)") (class "Default")
      (node (ref "U107") (pin "DIN") (pinfunction "DIN_DIN") (pintype "unspecified"))
      (node (ref "U108") (pin "OUT") (pinfunction "OUT_OUT") (pintype "unspecified"))
    )
    (net (code "137") (name "Net-(U107-PadOUT)") (class "Default")
      (node (ref "U107") (pin "OUT") (pinfunction "OUT_OUT") (pintype "unspecified"))
      (node (ref "U112") (pin "DIN") (pinfunction "DIN_DIN") (pintype "unspecified"))
    )
    (net (code "138") (name "Net-(U109-PadDIN)") (class "Default")
      (node (ref "U109") (pin "DIN") (pinfunction "DIN_DIN") (pintype "unspecified"))
      (node (ref "U111") (pin "OUT") (pinfunction "OUT_OUT") (pintype "unspecified"))
    )
    (net (code "139") (name "Net-(U109-PadOUT)") (class "Default")
      (node (ref "U109") (pin "OUT") (pinfunction "OUT_OUT") (pintype "unspecified"))
      (node (ref "U110") (pin "DIN") (pinfunction "DIN_DIN") (pintype "unspecified"))
    )
    (net (code "140") (name "Net-(U110-PadOUT)") (class "Default")
      (node (ref "U110") (pin "OUT") (pinfunction "OUT_OUT") (pintype "unspecified"))
      (node (ref "U136") (pin "DIN") (pinfunction "DIN_DIN") (pintype "unspecified"))
    )
    (net (code "141") (name "Net-(U111-PadDIN)") (class "Default")
      (node (ref "U111") (pin "DIN") (pinfunction "DIN_DIN") (pintype "unspecified"))
      (node (ref "U112") (pin "OUT") (pinfunction "OUT_OUT") (pintype "unspecified"))
    )
    (net (code "142") (name "Net-(U113-PadDIN)") (class "Default")
      (node (ref "U113") (pin "DIN") (pinfunction "DIN_DIN") (pintype "unspecified"))
      (node (ref "U118") (pin "OUT") (pinfunction "OUT_OUT") (pintype "unspecified"))
    )
    (net (code "143") (name "Net-(U113-PadOUT)") (class "Default")
      (node (ref "U113") (pin "OUT") (pinfunction "OUT_OUT") (pintype "unspecified"))
      (node (ref "U114") (pin "DIN") (pinfunction "DIN_DIN") (pintype "unspecified"))
    )
    (net (code "144") (name "Net-(U114-PadOUT)") (class "Default")
      (node (ref "U114") (pin "OUT") (pinfunction "OUT_OUT") (pintype "unspecified"))
      (node (ref "U116") (pin "DIN") (pinfunction "DIN_DIN") (pintype "unspecified"))
    )
    (net (code "145") (name "Net-(U115-PadDIN)") (class "Default")
      (node (ref "U115") (pin "DIN") (pinfunction "DIN_DIN") (pintype "unspecified"))
      (node (ref "U116") (pin "OUT") (pinfunction "OUT_OUT") (pintype "unspecified"))
    )
    (net (code "146") (name "Net-(U117-PadDIN)") (class "Default")
      (node (ref "U117") (pin "DIN") (pinfunction "DIN_DIN") (pintype "unspecified"))
      (node (ref "U119") (pin "OUT") (pinfunction "OUT_OUT") (pintype "unspecified"))
    )
    (net (code "147") (name "Net-(U117-PadOUT)") (class "Default")
      (node (ref "U117") (pin "OUT") (pinfunction "OUT_OUT") (pintype "unspecified"))
      (node (ref "U118") (pin "DIN") (pinfunction "DIN_DIN") (pintype "unspecified"))
    )
    (net (code "148") (name "Net-(U119-PadDIN)") (class "Default")
      (node (ref "U119") (pin "DIN") (pinfunction "DIN_DIN") (pintype "unspecified"))
      (node (ref "U120") (pin "OUT") (pinfunction "OUT_OUT") (pintype "unspecified"))
    )
    (net (code "149") (name "Net-(U121-PadDIN)") (class "Default")
      (node (ref "U121") (pin "DIN") (pinfunction "DIN_DIN") (pintype "unspecified"))
      (node (ref "U131") (pin "OUT") (pinfunction "OUT_OUT") (pintype "unspecified"))
    )
    (net (code "150") (name "Net-(U121-PadOUT)") (class "Default")
      (node (ref "U121") (pin "OUT") (pinfunction "OUT_OUT") (pintype "unspecified"))
      (node (ref "U122") (pin "DIN") (pinfunction "DIN_DIN") (pintype "unspecified"))
    )
    (net (code "151") (name "Net-(U122-PadOUT)") (class "Default")
      (node (ref "U122") (pin "OUT") (pinfunction "OUT_OUT") (pintype "unspecified"))
      (node (ref "U124") (pin "DIN") (pinfunction "DIN_DIN") (pintype "unspecified"))
    )
    (net (code "152") (name "Net-(U123-PadDIN)") (class "Default")
      (node (ref "U123") (pin "DIN") (pinfunction "DIN_DIN") (pintype "unspecified"))
      (node (ref "U124") (pin "OUT") (pinfunction "OUT_OUT") (pintype "unspecified"))
    )
    (net (code "153") (name "Net-(U123-PadOUT)") (class "Default")
      (node (ref "U123") (pin "OUT") (pinfunction "OUT_OUT") (pintype "unspecified"))
      (node (ref "U128") (pin "DIN") (pinfunction "DIN_DIN") (pintype "unspecified"))
    )
    (net (code "154") (name "Net-(U125-PadDIN)") (class "Default")
      (node (ref "U125") (pin "DIN") (pinfunction "DIN_DIN") (pintype "unspecified"))
      (node (ref "U127") (pin "OUT") (pinfunction "OUT_OUT") (pintype "unspecified"))
    )
    (net (code "155") (name "Net-(U125-PadOUT)") (class "Default")
      (node (ref "U125") (pin "OUT") (pinfunction "OUT_OUT") (pintype "unspecified"))
      (node (ref "U126") (pin "DIN") (pinfunction "DIN_DIN") (pintype "unspecified"))
    )
    (net (code "156") (name "Net-(U126-PadOUT)") (class "Default")
      (node (ref "U126") (pin "OUT") (pinfunction "OUT_OUT") (pintype "unspecified"))
      (node (ref "U152") (pin "DIN") (pinfunction "DIN_DIN") (pintype "unspecified"))
    )
    (net (code "157") (name "Net-(U127-PadDIN)") (class "Default")
      (node (ref "U127") (pin "DIN") (pinfunction "DIN_DIN") (pintype "unspecified"))
      (node (ref "U128") (pin "OUT") (pinfunction "OUT_OUT") (pintype "unspecified"))
    )
    (net (code "158") (name "Net-(U129-PadDIN)") (class "Default")
      (node (ref "U129") (pin "DIN") (pinfunction "DIN_DIN") (pintype "unspecified"))
      (node (ref "U134") (pin "OUT") (pinfunction "OUT_OUT") (pintype "unspecified"))
    )
    (net (code "159") (name "Net-(U129-PadOUT)") (class "Default")
      (node (ref "U129") (pin "OUT") (pinfunction "OUT_OUT") (pintype "unspecified"))
      (node (ref "U130") (pin "DIN") (pinfunction "DIN_DIN") (pintype "unspecified"))
    )
    (net (code "160") (name "Net-(U130-PadOUT)") (class "Default")
      (node (ref "U130") (pin "OUT") (pinfunction "OUT_OUT") (pintype "unspecified"))
      (node (ref "U132") (pin "DIN") (pinfunction "DIN_DIN") (pintype "unspecified"))
    )
    (net (code "161") (name "Net-(U131-PadDIN)") (class "Default")
      (node (ref "U131") (pin "DIN") (pinfunction "DIN_DIN") (pintype "unspecified"))
      (node (ref "U132") (pin "OUT") (pinfunction "OUT_OUT") (pintype "unspecified"))
    )
    (net (code "162") (name "Net-(U133-PadDIN)") (class "Default")
      (node (ref "U133") (pin "DIN") (pinfunction "DIN_DIN") (pintype "unspecified"))
      (node (ref "U135") (pin "OUT") (pinfunction "OUT_OUT") (pintype "unspecified"))
    )
    (net (code "163") (name "Net-(U133-PadOUT)") (class "Default")
      (node (ref "U133") (pin "OUT") (pinfunction "OUT_OUT") (pintype "unspecified"))
      (node (ref "U134") (pin "DIN") (pinfunction "DIN_DIN") (pintype "unspecified"))
    )
    (net (code "164") (name "Net-(U135-PadDIN)") (class "Default")
      (node (ref "U135") (pin "DIN") (pinfunction "DIN_DIN") (pintype "unspecified"))
      (node (ref "U136") (pin "OUT") (pinfunction "OUT_OUT") (pintype "unspecified"))
    )
    (net (code "165") (name "Net-(U137-PadDIN)") (class "Default")
      (node (ref "U137") (pin "DIN") (pinfunction "DIN_DIN") (pintype "unspecified"))
      (node (ref "U147") (pin "OUT") (pinfunction "OUT_OUT") (pintype "unspecified"))
    )
    (net (code "166") (name "Net-(U137-PadOUT)") (class "Default")
      (node (ref "U137") (pin "OUT") (pinfunction "OUT_OUT") (pintype "unspecified"))
      (node (ref "U138") (pin "DIN") (pinfunction "DIN_DIN") (pintype "unspecified"))
    )
    (net (code "167") (name "Net-(U138-PadOUT)") (class "Default")
      (node (ref "U138") (pin "OUT") (pinfunction "OUT_OUT") (pintype "unspecified"))
      (node (ref "U140") (pin "DIN") (pinfunction "DIN_DIN") (pintype "unspecified"))
    )
    (net (code "168") (name "Net-(U139-PadDIN)") (class "Default")
      (node (ref "U139") (pin "DIN") (pinfunction "DIN_DIN") (pintype "unspecified"))
      (node (ref "U140") (pin "OUT") (pinfunction "OUT_OUT") (pintype "unspecified"))
    )
    (net (code "169") (name "Net-(U139-PadOUT)") (class "Default")
      (node (ref "U139") (pin "OUT") (pinfunction "OUT_OUT") (pintype "unspecified"))
      (node (ref "U144") (pin "DIN") (pinfunction "DIN_DIN") (pintype "unspecified"))
    )
    (net (code "170") (name "Net-(U141-PadDIN)") (class "Default")
      (node (ref "U141") (pin "DIN") (pinfunction "DIN_DIN") (pintype "unspecified"))
      (node (ref "U143") (pin "OUT") (pinfunction "OUT_OUT") (pintype "unspecified"))
    )
    (net (code "171") (name "Net-(U141-PadOUT)") (class "Default")
      (node (ref "U141") (pin "OUT") (pinfunction "OUT_OUT") (pintype "unspecified"))
      (node (ref "U142") (pin "DIN") (pinfunction "DIN_DIN") (pintype "unspecified"))
    )
    (net (code "172") (name "Net-(U142-PadOUT)") (class "Default")
      (node (ref "U142") (pin "OUT") (pinfunction "OUT_OUT") (pintype "unspecified"))
      (node (ref "U168") (pin "DIN") (pinfunction "DIN_DIN") (pintype "unspecified"))
    )
    (net (code "173") (name "Net-(U143-PadDIN)") (class "Default")
      (node (ref "U143") (pin "DIN") (pinfunction "DIN_DIN") (pintype "unspecified"))
      (node (ref "U144") (pin "OUT") (pinfunction "OUT_OUT") (pintype "unspecified"))
    )
    (net (code "174") (name "Net-(U145-PadDIN)") (class "Default")
      (node (ref "U145") (pin "DIN") (pinfunction "DIN_DIN") (pintype "unspecified"))
      (node (ref "U150") (pin "OUT") (pinfunction "OUT_OUT") (pintype "unspecified"))
    )
    (net (code "175") (name "Net-(U145-PadOUT)") (class "Default")
      (node (ref "U145") (pin "OUT") (pinfunction "OUT_OUT") (pintype "unspecified"))
      (node (ref "U146") (pin "DIN") (pinfunction "DIN_DIN") (pintype "unspecified"))
    )
    (net (code "176") (name "Net-(U146-PadOUT)") (class "Default")
      (node (ref "U146") (pin "OUT") (pinfunction "OUT_OUT") (pintype "unspecified"))
      (node (ref "U148") (pin "DIN") (pinfunction "DIN_DIN") (pintype "unspecified"))
    )
    (net (code "177") (name "Net-(U147-PadDIN)") (class "Default")
      (node (ref "U147") (pin "DIN") (pinfunction "DIN_DIN") (pintype "unspecified"))
      (node (ref "U148") (pin "OUT") (pinfunction "OUT_OUT") (pintype "unspecified"))
    )
    (net (code "178") (name "Net-(U149-PadDIN)") (class "Default")
      (node (ref "U149") (pin "DIN") (pinfunction "DIN_DIN") (pintype "unspecified"))
      (node (ref "U151") (pin "OUT") (pinfunction "OUT_OUT") (pintype "unspecified"))
    )
    (net (code "179") (name "Net-(U149-PadOUT)") (class "Default")
      (node (ref "U149") (pin "OUT") (pinfunction "OUT_OUT") (pintype "unspecified"))
      (node (ref "U150") (pin "DIN") (pinfunction "DIN_DIN") (pintype "unspecified"))
    )
    (net (code "180") (name "Net-(U151-PadDIN)") (class "Default")
      (node (ref "U151") (pin "DIN") (pinfunction "DIN_DIN") (pintype "unspecified"))
      (node (ref "U152") (pin "OUT") (pinfunction "OUT_OUT") (pintype "unspecified"))
    )
    (net (code "181") (name "Net-(U153-PadDIN)") (class "Default")
      (node (ref "U153") (pin "DIN") (pinfunction "DIN_DIN") (pintype "unspecified"))
      (node (ref "U163") (pin "OUT") (pinfunction "OUT_OUT") (pintype "unspecified"))
    )
    (net (code "182") (name "Net-(U153-PadOUT)") (class "Default")
      (node (ref "U153") (pin "OUT") (pinfunction "OUT_OUT") (pintype "unspecified"))
      (node (ref "U154") (pin "DIN") (pinfunction "DIN_DIN") (pintype "unspecified"))
    )
    (net (code "183") (name "Net-(U154-PadOUT)") (class "Default")
      (node (ref "U154") (pin "OUT") (pinfunction "OUT_OUT") (pintype "unspecified"))
      (node (ref "U156") (pin "DIN") (pinfunction "DIN_DIN") (pintype "unspecified"))
    )
    (net (code "184") (name "Net-(U155-PadDIN)") (class "Default")
      (node (ref "U155") (pin "DIN") (pinfunction "DIN_DIN") (pintype "unspecified"))
      (node (ref "U156") (pin "OUT") (pinfunction "OUT_OUT") (pintype "unspecified"))
    )
    (net (code "185") (name "Net-(U155-PadOUT)") (class "Default")
      (node (ref "U155") (pin "OUT") (pinfunction "OUT_OUT") (pintype "unspecified"))
      (node (ref "U160") (pin "DIN") (pinfunction "DIN_DIN") (pintype "unspecified"))
    )
    (net (code "186") (name "Net-(U157-PadDIN)") (class "Default")
      (node (ref "U157") (pin "DIN") (pinfunction "DIN_DIN") (pintype "unspecified"))
      (node (ref "U159") (pin "OUT") (pinfunction "OUT_OUT") (pintype "unspecified"))
    )
    (net (code "187") (name "Net-(U157-PadOUT)") (class "Default")
      (node (ref "U157") (pin "OUT") (pinfunction "OUT_OUT") (pintype "unspecified"))
      (node (ref "U158") (pin "DIN") (pinfunction "DIN_DIN") (pintype "unspecified"))
    )
    (net (code "188") (name "Net-(U158-PadOUT)") (class "Default")
      (node (ref "U158") (pin "OUT") (pinfunction "OUT_OUT") (pintype "unspecified"))
      (node (ref "U184") (pin "DIN") (pinfunction "DIN_DIN") (pintype "unspecified"))
    )
    (net (code "189") (name "Net-(U159-PadDIN)") (class "Default")
      (node (ref "U159") (pin "DIN") (pinfunction "DIN_DIN") (pintype "unspecified"))
      (node (ref "U160") (pin "OUT") (pinfunction "OUT_OUT") (pintype "unspecified"))
    )
    (net (code "190") (name "Net-(U161-PadDIN)") (class "Default")
      (node (ref "U161") (pin "DIN") (pinfunction "DIN_DIN") (pintype "unspecified"))
      (node (ref "U166") (pin "OUT") (pinfunction "OUT_OUT") (pintype "unspecified"))
    )
    (net (code "191") (name "Net-(U161-PadOUT)") (class "Default")
      (node (ref "U161") (pin "OUT") (pinfunction "OUT_OUT") (pintype "unspecified"))
      (node (ref "U162") (pin "DIN") (pinfunction "DIN_DIN") (pintype "unspecified"))
    )
    (net (code "192") (name "Net-(U162-PadOUT)") (class "Default")
      (node (ref "U162") (pin "OUT") (pinfunction "OUT_OUT") (pintype "unspecified"))
      (node (ref "U164") (pin "DIN") (pinfunction "DIN_DIN") (pintype "unspecified"))
    )
    (net (code "193") (name "Net-(U163-PadDIN)") (class "Default")
      (node (ref "U163") (pin "DIN") (pinfunction "DIN_DIN") (pintype "unspecified"))
      (node (ref "U164") (pin "OUT") (pinfunction "OUT_OUT") (pintype "unspecified"))
    )
    (net (code "194") (name "Net-(U165-PadDIN)") (class "Default")
      (node (ref "U165") (pin "DIN") (pinfunction "DIN_DIN") (pintype "unspecified"))
      (node (ref "U167") (pin "OUT") (pinfunction "OUT_OUT") (pintype "unspecified"))
    )
    (net (code "195") (name "Net-(U165-PadOUT)") (class "Default")
      (node (ref "U165") (pin "OUT") (pinfunction "OUT_OUT") (pintype "unspecified"))
      (node (ref "U166") (pin "DIN") (pinfunction "DIN_DIN") (pintype "unspecified"))
    )
    (net (code "196") (name "Net-(U167-PadDIN)") (class "Default")
      (node (ref "U167") (pin "DIN") (pinfunction "DIN_DIN") (pintype "unspecified"))
      (node (ref "U168") (pin "OUT") (pinfunction "OUT_OUT") (pintype "unspecified"))
    )
    (net (code "197") (name "Net-(U177-PadDIN)") (class "Default")
      (node (ref "U177") (pin "DIN") (pinfunction "DIN_DIN") (pintype "unspecified"))
      (node (ref "U182") (pin "OUT") (pinfunction "OUT_OUT") (pintype "unspecified"))
    )
    (net (code "198") (name "Net-(U177-PadOUT)") (class "Default")
      (node (ref "U177") (pin "OUT") (pinfunction "OUT_OUT") (pintype "unspecified"))
      (node (ref "U178") (pin "DIN") (pinfunction "DIN_DIN") (pintype "unspecified"))
    )
    (net (code "199") (name "Net-(U181-PadDIN)") (class "Default")
      (node (ref "U181") (pin "DIN") (pinfunction "DIN_DIN") (pintype "unspecified"))
      (node (ref "U183") (pin "OUT") (pinfunction "OUT_OUT") (pintype "unspecified"))
    )
    (net (code "200") (name "Net-(U181-PadOUT)") (class "Default")
      (node (ref "U181") (pin "OUT") (pinfunction "OUT_OUT") (pintype "unspecified"))
      (node (ref "U182") (pin "DIN") (pinfunction "DIN_DIN") (pintype "unspecified"))
    )
    (net (code "201") (name "Net-(U183-PadDIN)") (class "Default")
      (node (ref "U183") (pin "DIN") (pinfunction "DIN_DIN") (pintype "unspecified"))
      (node (ref "U184") (pin "OUT") (pinfunction "OUT_OUT") (pintype "unspecified"))
    )
    (net (code "202") (name "VCC") (class "Default")
      (node (ref "U103") (pin "36") (pinfunction "3V3_OUT_36") (pintype "output"))
      (node (ref "U104") (pin "1") (pinfunction "1_1") (pintype "unspecified"))
      (node (ref "U104") (pin "7") (pinfunction "7_7") (pintype "unspecified"))
    )
    (net (code "203") (name "unconnected-(SW1-EH-Pad6)") (class "Default")
      (node (ref "SW1") (pin "6") (pinfunction "EH_6") (pintype "unspecified+no_connect"))
    )
    (net (code "204") (name "unconnected-(SW1-EH-Pad7)") (class "Default")
      (node (ref "SW1") (pin "7") (pinfunction "EH_7") (pintype "unspecified+no_connect"))
    )
    (net (code "205") (name "unconnected-(U103-3V3_EN-Pad37)") (class "Default")
      (node (ref "U103") (pin "37") (pinfunction "3V3_EN_37") (pintype "unspecified+no_connect"))
    )
    (net (code "206") (name "unconnected-(U103-GND-Pad42)") (class "Default")
      (node (ref "U103") (pin "42") (pinfunction "GND_42") (pintype "unspecified+no_connect"))
    )
    (net (code "207") (name "unconnected-(U103-RUN-Pad30)") (class "Default")
      (node (ref "U103") (pin "30") (pinfunction "RUN_30") (pintype "unspecified+no_connect"))
    )
    (net (code "208") (name "unconnected-(U103-SWCLK-Pad41)") (class "Default")
      (node (ref "U103") (pin "41") (pinfunction "SWCLK_41") (pintype "unspecified+no_connect"))
    )
    (net (code "209") (name "unconnected-(U103-SWDIO-Pad43)") (class "Default")
      (node (ref "U103") (pin "43") (pinfunction "SWDIO_43") (pintype "unspecified+no_connect"))
    )
    (net (code "210") (name "unconnected-(U103-VSYS-Pad39)") (class "Default")
      (node (ref "U103") (pin "39") (pinfunction "VSYS_39") (pintype "unspecified+no_connect"))
    )
    (net (code "211") (name "unconnected-(U178-PadOUT)") (class "Default")
      (node (ref "U178") (pin "OUT") (pinfunction "OUT_OUT") (pintype "unspecified+no_connect"))
    )
  )
)
